# Display_LED_Monitor.net
KiCad netlist of a schematic drawn in Altium Designer
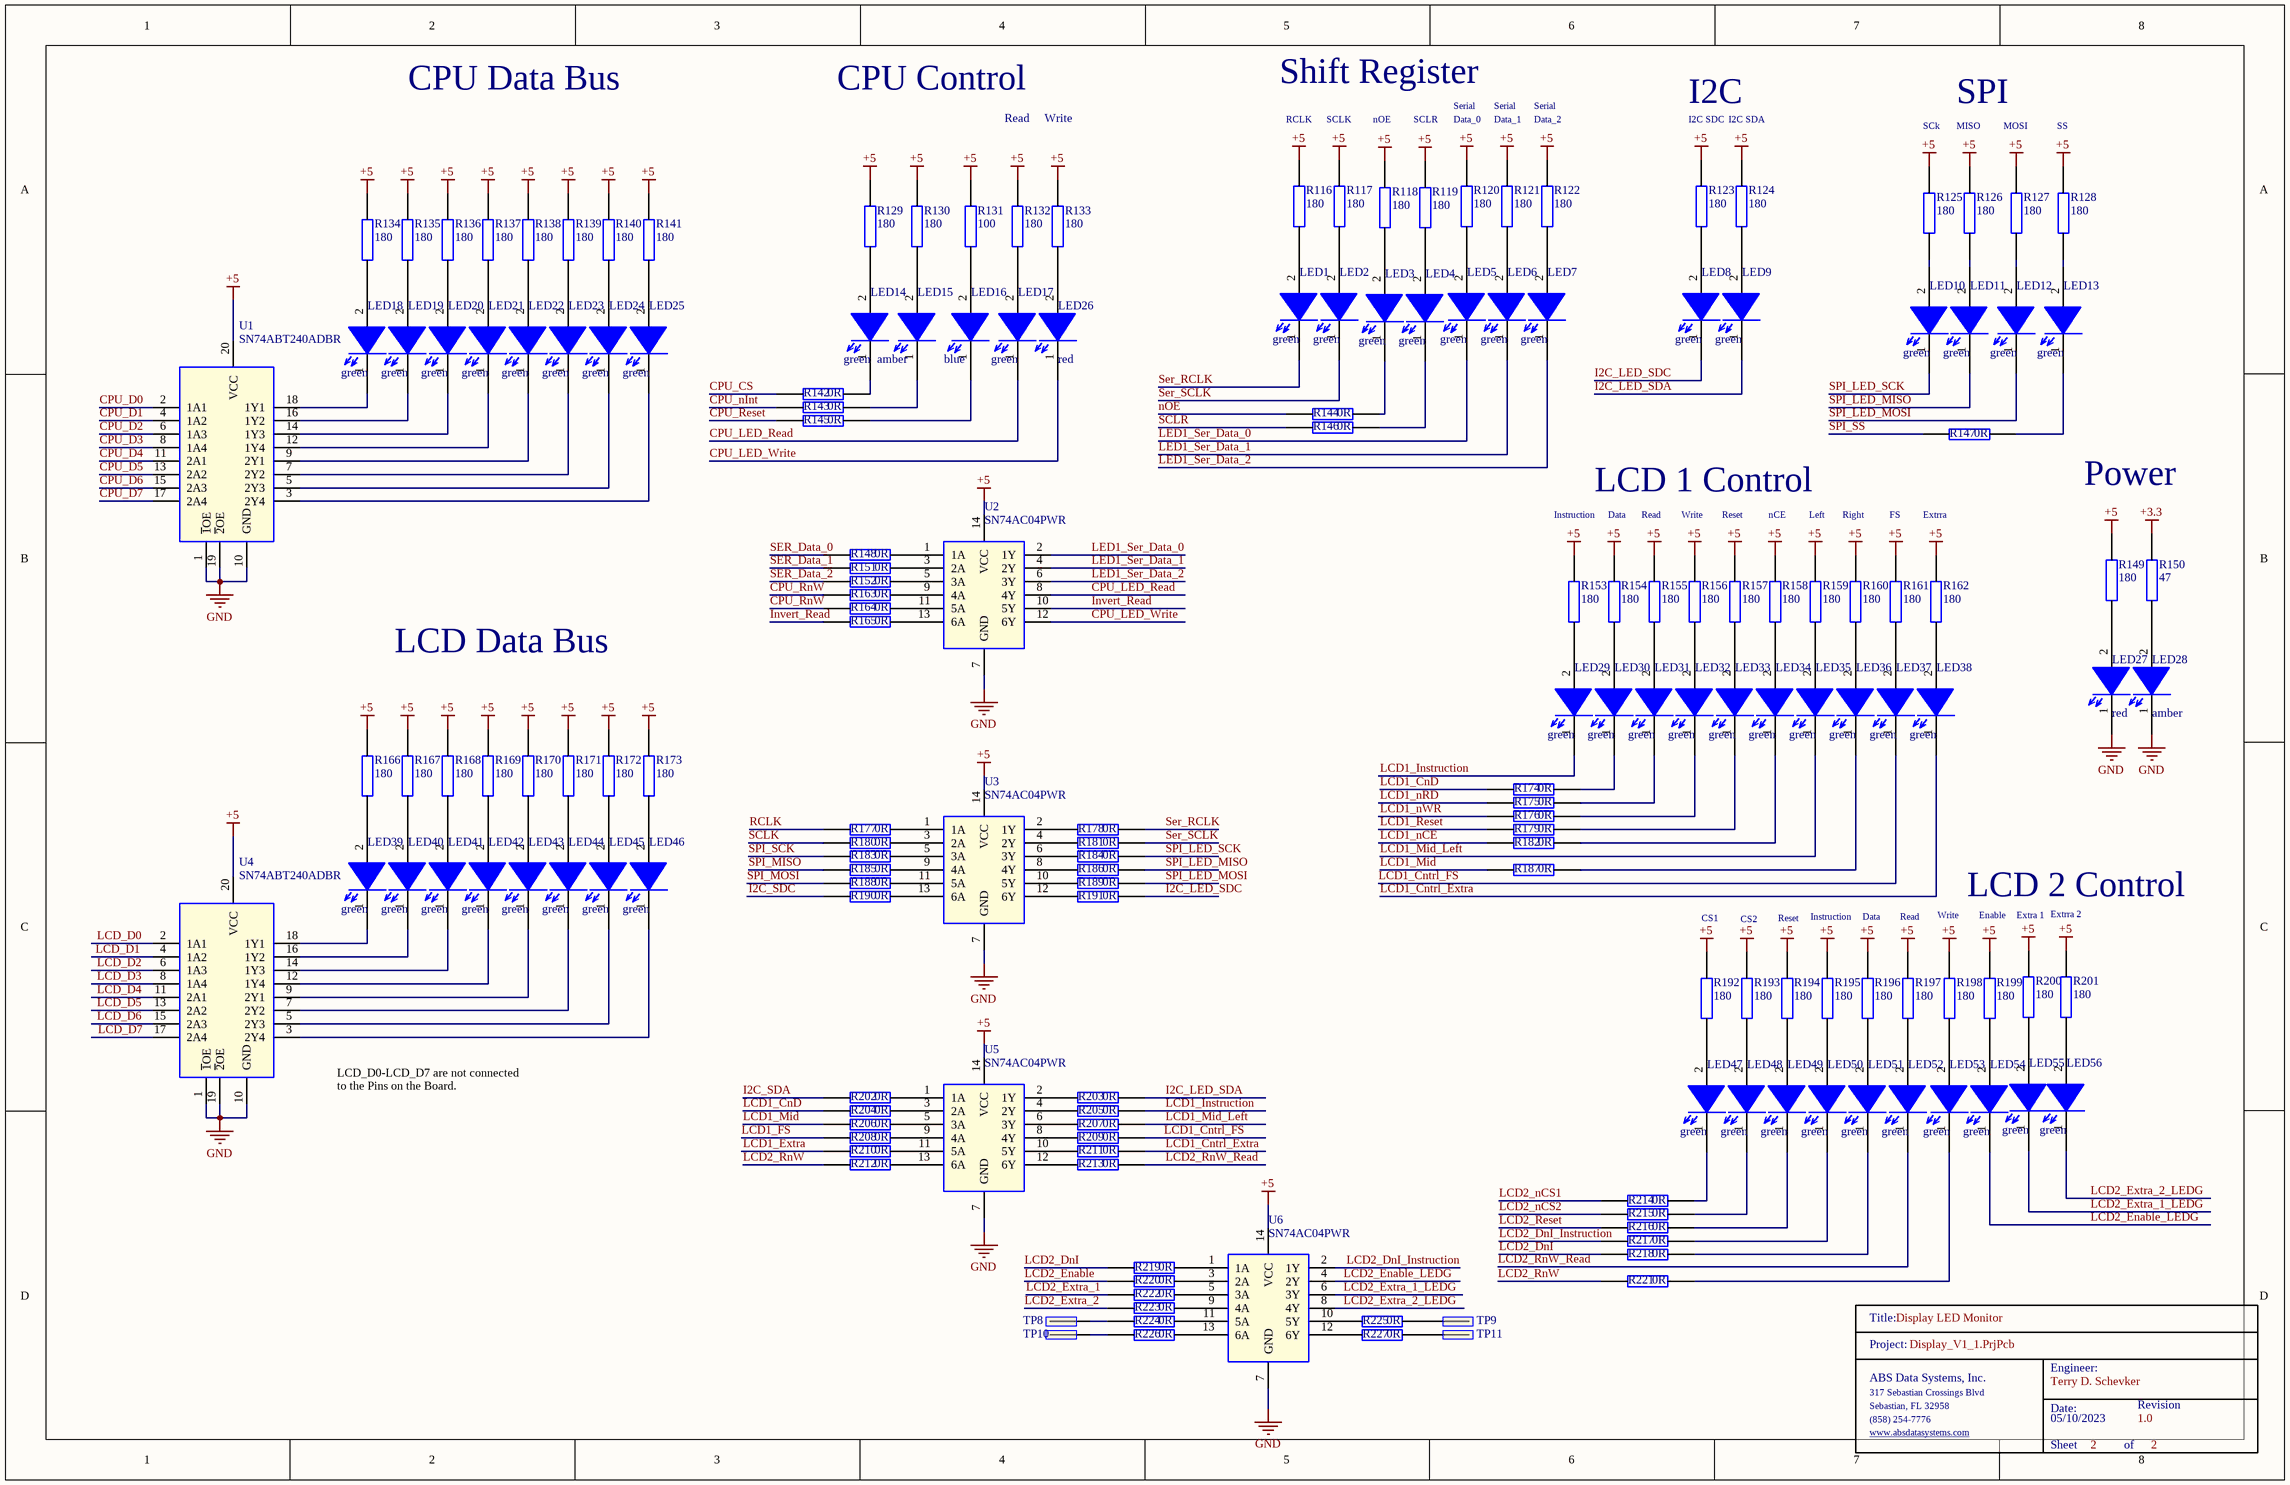
[diagram p0: Display_LED_Monitor.SchDoc]

(export (version "E")
  (design (tool "Eeschema 10.0.6"))
  (components
    (comp (ref "LED1")
      (value "green")
      (footprint "0603_Diode")
      (description "Wurth Elektronik 0603 green")
      (fields
        (field (name "MANUFACTURER") "Wurth Electronics")
        (field (name "MANUFACTURER PART NUMBER") "150060GS75000")
      )
      (libsource (lib "Misc") (part "150060GS75000"))
    )
    (comp (ref "LED2")
      (value "green")
      (footprint "0603_Diode")
      (description "Wurth Elektronik 0603 green")
      (fields
        (field (name "MANUFACTURER") "Wurth Electronics")
        (field (name "MANUFACTURER PART NUMBER") "150060GS75000")
      )
      (libsource (lib "Misc") (part "150060GS75000"))
    )
    (comp (ref "LED3")
      (value "green")
      (footprint "0603_Diode")
      (description "Wurth Elektronik 0603 green")
      (fields
        (field (name "MANUFACTURER") "Wurth Electronics")
        (field (name "MANUFACTURER PART NUMBER") "150060GS75000")
      )
      (libsource (lib "Misc") (part "150060GS75000"))
    )
    (comp (ref "LED4")
      (value "green")
      (footprint "0603_Diode")
      (description "Wurth Elektronik 0603 green")
      (fields
        (field (name "MANUFACTURER") "Wurth Electronics")
        (field (name "MANUFACTURER PART NUMBER") "150060GS75000")
      )
      (libsource (lib "Misc") (part "150060GS75000"))
    )
    (comp (ref "LED5")
      (value "green")
      (footprint "0603_Diode")
      (description "Wurth Elektronik 0603 green")
      (fields
        (field (name "MANUFACTURER") "Wurth Electronics")
        (field (name "MANUFACTURER PART NUMBER") "150060GS75000")
      )
      (libsource (lib "Misc") (part "150060GS75000"))
    )
    (comp (ref "LED6")
      (value "green")
      (footprint "0603_Diode")
      (description "Wurth Elektronik 0603 green")
      (fields
        (field (name "MANUFACTURER") "Wurth Electronics")
        (field (name "MANUFACTURER PART NUMBER") "150060GS75000")
      )
      (libsource (lib "Misc") (part "150060GS75000"))
    )
    (comp (ref "LED7")
      (value "green")
      (footprint "0603_Diode")
      (description "Wurth Elektronik 0603 green")
      (fields
        (field (name "MANUFACTURER") "Wurth Electronics")
        (field (name "MANUFACTURER PART NUMBER") "150060GS75000")
      )
      (libsource (lib "Misc") (part "150060GS75000"))
    )
    (comp (ref "LED8")
      (value "green")
      (footprint "0603_Diode")
      (description "Wurth Elektronik 0603 green")
      (fields
        (field (name "MANUFACTURER") "Wurth Electronics")
        (field (name "MANUFACTURER PART NUMBER") "150060GS75000")
      )
      (libsource (lib "Misc") (part "150060GS75000"))
    )
    (comp (ref "LED9")
      (value "green")
      (footprint "0603_Diode")
      (description "Wurth Elektronik 0603 green")
      (fields
        (field (name "MANUFACTURER") "Wurth Electronics")
        (field (name "MANUFACTURER PART NUMBER") "150060GS75000")
      )
      (libsource (lib "Misc") (part "150060GS75000"))
    )
    (comp (ref "LED10")
      (value "green")
      (footprint "0603_Diode")
      (description "Wurth Elektronik 0603 green")
      (fields
        (field (name "MANUFACTURER") "Wurth Electronics")
        (field (name "MANUFACTURER PART NUMBER") "150060GS75000")
      )
      (libsource (lib "Misc") (part "150060GS75000"))
    )
    (comp (ref "LED11")
      (value "green")
      (footprint "0603_Diode")
      (description "Wurth Elektronik 0603 green")
      (fields
        (field (name "MANUFACTURER") "Wurth Electronics")
        (field (name "MANUFACTURER PART NUMBER") "150060GS75000")
      )
      (libsource (lib "Misc") (part "150060GS75000"))
    )
    (comp (ref "LED12")
      (value "green")
      (footprint "0603_Diode")
      (description "Wurth Elektronik 0603 green")
      (fields
        (field (name "MANUFACTURER") "Wurth Electronics")
        (field (name "MANUFACTURER PART NUMBER") "150060GS75000")
      )
      (libsource (lib "Misc") (part "150060GS75000"))
    )
    (comp (ref "LED13")
      (value "green")
      (footprint "0603_Diode")
      (description "Wurth Elektronik 0603 green")
      (fields
        (field (name "MANUFACTURER") "Wurth Electronics")
        (field (name "MANUFACTURER PART NUMBER") "150060GS75000")
      )
      (libsource (lib "Misc") (part "150060GS75000"))
    )
    (comp (ref "LED14")
      (value "green")
      (footprint "0603_Diode")
      (description "Wurth Elektronik 0603 green")
      (fields
        (field (name "MANUFACTURER") "Wurth Electronics")
        (field (name "MANUFACTURER PART NUMBER") "150060GS75000")
      )
      (libsource (lib "Misc") (part "150060GS75000"))
    )
    (comp (ref "LED15")
      (value "amber")
      (footprint "0603_Diode")
      (description "Wurth Elektronik 0603 amber")
      (fields
        (field (name "MANUFACTURER") "Wurth Electronics")
        (field (name "MANUFACTURER PART NUMBER") "150060GS75000")
      )
      (libsource (lib "Misc") (part "150060AS75000"))
    )
    (comp (ref "LED16")
      (value "blue")
      (footprint "0603_Diode")
      (description "Wurth Elektronik 0603 blue")
      (fields
        (field (name "MANUFACTURER") "Wurth Electronics")
        (field (name "MANUFACTURER PART NUMBER") "150060GS75000")
      )
      (libsource (lib "Misc") (part "150060BS75000"))
    )
    (comp (ref "LED17")
      (value "green")
      (footprint "0603_Diode")
      (description "Wurth Elektronik 0603 green")
      (fields
        (field (name "MANUFACTURER") "Wurth Electronics")
        (field (name "MANUFACTURER PART NUMBER") "150060GS75000")
      )
      (libsource (lib "Misc") (part "150060GS75000"))
    )
    (comp (ref "LED18")
      (value "green")
      (footprint "0603_Diode")
      (description "Wurth Elektronik 0603 green")
      (fields
        (field (name "MANUFACTURER") "Wurth Electronics")
        (field (name "MANUFACTURER PART NUMBER") "150060GS75000")
      )
      (libsource (lib "Misc") (part "150060GS75000"))
    )
    (comp (ref "LED19")
      (value "green")
      (footprint "0603_Diode")
      (description "Wurth Elektronik 0603 green")
      (fields
        (field (name "MANUFACTURER") "Wurth Electronics")
        (field (name "MANUFACTURER PART NUMBER") "150060GS75000")
      )
      (libsource (lib "Misc") (part "150060GS75000"))
    )
    (comp (ref "LED20")
      (value "green")
      (footprint "0603_Diode")
      (description "Wurth Elektronik 0603 green")
      (fields
        (field (name "MANUFACTURER") "Wurth Electronics")
        (field (name "MANUFACTURER PART NUMBER") "150060GS75000")
      )
      (libsource (lib "Misc") (part "150060GS75000"))
    )
    (comp (ref "LED21")
      (value "green")
      (footprint "0603_Diode")
      (description "Wurth Elektronik 0603 green")
      (fields
        (field (name "MANUFACTURER") "Wurth Electronics")
        (field (name "MANUFACTURER PART NUMBER") "150060GS75000")
      )
      (libsource (lib "Misc") (part "150060GS75000"))
    )
    (comp (ref "LED22")
      (value "green")
      (footprint "0603_Diode")
      (description "Wurth Elektronik 0603 green")
      (fields
        (field (name "MANUFACTURER") "Wurth Electronics")
        (field (name "MANUFACTURER PART NUMBER") "150060GS75000")
      )
      (libsource (lib "Misc") (part "150060GS75000"))
    )
    (comp (ref "LED23")
      (value "green")
      (footprint "0603_Diode")
      (description "Wurth Elektronik 0603 green")
      (fields
        (field (name "MANUFACTURER") "Wurth Electronics")
        (field (name "MANUFACTURER PART NUMBER") "150060GS75000")
      )
      (libsource (lib "Misc") (part "150060GS75000"))
    )
    (comp (ref "LED24")
      (value "green")
      (footprint "0603_Diode")
      (description "Wurth Elektronik 0603 green")
      (fields
        (field (name "MANUFACTURER") "Wurth Electronics")
        (field (name "MANUFACTURER PART NUMBER") "150060GS75000")
      )
      (libsource (lib "Misc") (part "150060GS75000"))
    )
    (comp (ref "LED25")
      (value "green")
      (footprint "0603_Diode")
      (description "Wurth Elektronik 0603 green")
      (fields
        (field (name "MANUFACTURER") "Wurth Electronics")
        (field (name "MANUFACTURER PART NUMBER") "150060GS75000")
      )
      (libsource (lib "Misc") (part "150060GS75000"))
    )
    (comp (ref "LED26")
      (value "red")
      (footprint "0603_Diode")
      (description "Wurth Elektronik 0603 red")
      (fields
        (field (name "MANUFACTURER") "Wurth Electronics")
        (field (name "MANUFACTURER PART NUMBER") "150060GS75000")
      )
      (libsource (lib "Misc") (part "150060RS75000"))
    )
    (comp (ref "LED27")
      (value "red")
      (footprint "0603_Diode")
      (description "Wurth Elektronik 0603 red")
      (fields
        (field (name "MANUFACTURER") "Wurth Electronics")
        (field (name "MANUFACTURER PART NUMBER") "150060GS75000")
      )
      (libsource (lib "Misc") (part "150060RS75000"))
    )
    (comp (ref "LED28")
      (value "amber")
      (footprint "0603_Diode")
      (description "Wurth Elektronik 0603 amber")
      (fields
        (field (name "MANUFACTURER") "Wurth Electronics")
        (field (name "MANUFACTURER PART NUMBER") "150060GS75000")
      )
      (libsource (lib "Misc") (part "150060AS75000"))
    )
    (comp (ref "LED29")
      (value "green")
      (footprint "0603_Diode")
      (description "Wurth Elektronik 0603 green")
      (fields
        (field (name "MANUFACTURER") "Wurth Electronics")
        (field (name "MANUFACTURER PART NUMBER") "150060GS75000")
      )
      (libsource (lib "Misc") (part "150060GS75000"))
    )
    (comp (ref "LED30")
      (value "green")
      (footprint "0603_Diode")
      (description "Wurth Elektronik 0603 green")
      (fields
        (field (name "MANUFACTURER") "Wurth Electronics")
        (field (name "MANUFACTURER PART NUMBER") "150060GS75000")
      )
      (libsource (lib "Misc") (part "150060GS75000"))
    )
    (comp (ref "LED31")
      (value "green")
      (footprint "0603_Diode")
      (description "Wurth Elektronik 0603 green")
      (fields
        (field (name "MANUFACTURER") "Wurth Electronics")
        (field (name "MANUFACTURER PART NUMBER") "150060GS75000")
      )
      (libsource (lib "Misc") (part "150060GS75000"))
    )
    (comp (ref "LED32")
      (value "green")
      (footprint "0603_Diode")
      (description "Wurth Elektronik 0603 green")
      (fields
        (field (name "MANUFACTURER") "Wurth Electronics")
        (field (name "MANUFACTURER PART NUMBER") "150060GS75000")
      )
      (libsource (lib "Misc") (part "150060GS75000"))
    )
    (comp (ref "LED33")
      (value "green")
      (footprint "0603_Diode")
      (description "Wurth Elektronik 0603 green")
      (fields
        (field (name "MANUFACTURER") "Wurth Electronics")
        (field (name "MANUFACTURER PART NUMBER") "150060GS75000")
      )
      (libsource (lib "Misc") (part "150060GS75000"))
    )
    (comp (ref "LED34")
      (value "green")
      (footprint "0603_Diode")
      (description "Wurth Elektronik 0603 green")
      (fields
        (field (name "MANUFACTURER") "Wurth Electronics")
        (field (name "MANUFACTURER PART NUMBER") "150060GS75000")
      )
      (libsource (lib "Misc") (part "150060GS75000"))
    )
    (comp (ref "LED35")
      (value "green")
      (footprint "0603_Diode")
      (description "Wurth Elektronik 0603 green")
      (fields
        (field (name "MANUFACTURER") "Wurth Electronics")
        (field (name "MANUFACTURER PART NUMBER") "150060GS75000")
      )
      (libsource (lib "Misc") (part "150060GS75000"))
    )
    (comp (ref "LED36")
      (value "green")
      (footprint "0603_Diode")
      (description "Wurth Elektronik 0603 green")
      (fields
        (field (name "MANUFACTURER") "Wurth Electronics")
        (field (name "MANUFACTURER PART NUMBER") "150060GS75000")
      )
      (libsource (lib "Misc") (part "150060GS75000"))
    )
    (comp (ref "LED37")
      (value "green")
      (footprint "0603_Diode")
      (description "Wurth Elektronik 0603 green")
      (fields
        (field (name "MANUFACTURER") "Wurth Electronics")
        (field (name "MANUFACTURER PART NUMBER") "150060GS75000")
      )
      (libsource (lib "Misc") (part "150060GS75000"))
    )
    (comp (ref "LED38")
      (value "green")
      (footprint "0603_Diode")
      (description "Wurth Elektronik 0603 green")
      (fields
        (field (name "MANUFACTURER") "Wurth Electronics")
        (field (name "MANUFACTURER PART NUMBER") "150060GS75000")
      )
      (libsource (lib "Misc") (part "150060GS75000"))
    )
    (comp (ref "LED39")
      (value "green")
      (footprint "0603_Diode")
      (description "Wurth Elektronik 0603 green")
      (fields
        (field (name "MANUFACTURER") "Wurth Electronics")
        (field (name "MANUFACTURER PART NUMBER") "150060GS75000")
      )
      (libsource (lib "Misc") (part "150060GS75000"))
    )
    (comp (ref "LED40")
      (value "green")
      (footprint "0603_Diode")
      (description "Wurth Elektronik 0603 green")
      (fields
        (field (name "MANUFACTURER") "Wurth Electronics")
        (field (name "MANUFACTURER PART NUMBER") "150060GS75000")
      )
      (libsource (lib "Misc") (part "150060GS75000"))
    )
    (comp (ref "LED41")
      (value "green")
      (footprint "0603_Diode")
      (description "Wurth Elektronik 0603 green")
      (fields
        (field (name "MANUFACTURER") "Wurth Electronics")
        (field (name "MANUFACTURER PART NUMBER") "150060GS75000")
      )
      (libsource (lib "Misc") (part "150060GS75000"))
    )
    (comp (ref "LED42")
      (value "green")
      (footprint "0603_Diode")
      (description "Wurth Elektronik 0603 green")
      (fields
        (field (name "MANUFACTURER") "Wurth Electronics")
        (field (name "MANUFACTURER PART NUMBER") "150060GS75000")
      )
      (libsource (lib "Misc") (part "150060GS75000"))
    )
    (comp (ref "LED43")
      (value "green")
      (footprint "0603_Diode")
      (description "Wurth Elektronik 0603 green")
      (fields
        (field (name "MANUFACTURER") "Wurth Electronics")
        (field (name "MANUFACTURER PART NUMBER") "150060GS75000")
      )
      (libsource (lib "Misc") (part "150060GS75000"))
    )
    (comp (ref "LED44")
      (value "green")
      (footprint "0603_Diode")
      (description "Wurth Elektronik 0603 green")
      (fields
        (field (name "MANUFACTURER") "Wurth Electronics")
        (field (name "MANUFACTURER PART NUMBER") "150060GS75000")
      )
      (libsource (lib "Misc") (part "150060GS75000"))
    )
    (comp (ref "LED45")
      (value "green")
      (footprint "0603_Diode")
      (description "Wurth Elektronik 0603 green")
      (fields
        (field (name "MANUFACTURER") "Wurth Electronics")
        (field (name "MANUFACTURER PART NUMBER") "150060GS75000")
      )
      (libsource (lib "Misc") (part "150060GS75000"))
    )
    (comp (ref "LED46")
      (value "green")
      (footprint "0603_Diode")
      (description "Wurth Elektronik 0603 green")
      (fields
        (field (name "MANUFACTURER") "Wurth Electronics")
        (field (name "MANUFACTURER PART NUMBER") "150060GS75000")
      )
      (libsource (lib "Misc") (part "150060GS75000"))
    )
    (comp (ref "LED47")
      (value "green")
      (footprint "0603_Diode")
      (description "Wurth Elektronik 0603 green")
      (fields
        (field (name "MANUFACTURER") "Wurth Electronics")
        (field (name "MANUFACTURER PART NUMBER") "150060GS75000")
      )
      (libsource (lib "Misc") (part "150060GS75000"))
    )
    (comp (ref "LED48")
      (value "green")
      (footprint "0603_Diode")
      (description "Wurth Elektronik 0603 green")
      (fields
        (field (name "MANUFACTURER") "Wurth Electronics")
        (field (name "MANUFACTURER PART NUMBER") "150060GS75000")
      )
      (libsource (lib "Misc") (part "150060GS75000"))
    )
    (comp (ref "LED49")
      (value "green")
      (footprint "0603_Diode")
      (description "Wurth Elektronik 0603 green")
      (fields
        (field (name "MANUFACTURER") "Wurth Electronics")
        (field (name "MANUFACTURER PART NUMBER") "150060GS75000")
      )
      (libsource (lib "Misc") (part "150060GS75000"))
    )
    (comp (ref "LED50")
      (value "green")
      (footprint "0603_Diode")
      (description "Wurth Elektronik 0603 green")
      (fields
        (field (name "MANUFACTURER") "Wurth Electronics")
        (field (name "MANUFACTURER PART NUMBER") "150060GS75000")
      )
      (libsource (lib "Misc") (part "150060GS75000"))
    )
    (comp (ref "LED51")
      (value "green")
      (footprint "0603_Diode")
      (description "Wurth Elektronik 0603 green")
      (fields
        (field (name "MANUFACTURER") "Wurth Electronics")
        (field (name "MANUFACTURER PART NUMBER") "150060GS75000")
      )
      (libsource (lib "Misc") (part "150060GS75000"))
    )
    (comp (ref "LED52")
      (value "green")
      (footprint "0603_Diode")
      (description "Wurth Elektronik 0603 green")
      (fields
        (field (name "MANUFACTURER") "Wurth Electronics")
        (field (name "MANUFACTURER PART NUMBER") "150060GS75000")
      )
      (libsource (lib "Misc") (part "150060GS75000"))
    )
    (comp (ref "LED53")
      (value "green")
      (footprint "0603_Diode")
      (description "Wurth Elektronik 0603 green")
      (fields
        (field (name "MANUFACTURER") "Wurth Electronics")
        (field (name "MANUFACTURER PART NUMBER") "150060GS75000")
      )
      (libsource (lib "Misc") (part "150060GS75000"))
    )
    (comp (ref "LED54")
      (value "green")
      (footprint "0603_Diode")
      (description "Wurth Elektronik 0603 green")
      (fields
        (field (name "MANUFACTURER") "Wurth Electronics")
        (field (name "MANUFACTURER PART NUMBER") "150060GS75000")
      )
      (libsource (lib "Misc") (part "150060GS75000"))
    )
    (comp (ref "LED55")
      (value "green")
      (footprint "0603_Diode")
      (description "Wurth Elektronik 0603 green")
      (fields
        (field (name "MANUFACTURER") "Wurth Electronics")
        (field (name "MANUFACTURER PART NUMBER") "150060GS75000")
      )
      (libsource (lib "Misc") (part "150060GS75000"))
    )
    (comp (ref "LED56")
      (value "green")
      (footprint "0603_Diode")
      (description "Wurth Elektronik 0603 green")
      (fields
        (field (name "MANUFACTURER") "Wurth Electronics")
        (field (name "MANUFACTURER PART NUMBER") "150060GS75000")
      )
      (libsource (lib "Misc") (part "150060GS75000"))
    )
    (comp (ref "R116")
      (value "180")
      (footprint "0603")
      (description "YAGEO 0603 180 ohm")
      (fields
        (field (name "MOUSER PART NUMBER") "603-RC0603JR-070RL")
        (field (name "MANUFACTURER_PART_NUMBER") "RC0603JR-070RL")
      )
      (libsource (lib "Resistors") (part "RC0603FR-13180RL"))
    )
    (comp (ref "R117")
      (value "180")
      (footprint "0603")
      (description "YAGEO 0603 180 ohm")
      (fields
        (field (name "MOUSER PART NUMBER") "603-RC0603JR-070RL")
        (field (name "MANUFACTURER_PART_NUMBER") "RC0603JR-070RL")
      )
      (libsource (lib "Resistors") (part "RC0603FR-13180RL"))
    )
    (comp (ref "R118")
      (value "180")
      (footprint "0603")
      (description "YAGEO 0603 180 ohm")
      (fields
        (field (name "MOUSER PART NUMBER") "603-RC0603JR-070RL")
        (field (name "MANUFACTURER_PART_NUMBER") "RC0603JR-070RL")
      )
      (libsource (lib "Resistors") (part "RC0603FR-13180RL"))
    )
    (comp (ref "R119")
      (value "180")
      (footprint "0603")
      (description "YAGEO 0603 180 ohm")
      (fields
        (field (name "MOUSER PART NUMBER") "603-RC0603JR-070RL")
        (field (name "MANUFACTURER_PART_NUMBER") "RC0603JR-070RL")
      )
      (libsource (lib "Resistors") (part "RC0603FR-13180RL"))
    )
    (comp (ref "R120")
      (value "180")
      (footprint "0603")
      (description "YAGEO 0603 180 ohm")
      (fields
        (field (name "MOUSER PART NUMBER") "603-RC0603JR-070RL")
        (field (name "MANUFACTURER_PART_NUMBER") "RC0603JR-070RL")
      )
      (libsource (lib "Resistors") (part "RC0603FR-13180RL"))
    )
    (comp (ref "R121")
      (value "180")
      (footprint "0603")
      (description "YAGEO 0603 180 ohm")
      (fields
        (field (name "MOUSER PART NUMBER") "603-RC0603JR-070RL")
        (field (name "MANUFACTURER_PART_NUMBER") "RC0603JR-070RL")
      )
      (libsource (lib "Resistors") (part "RC0603FR-13180RL"))
    )
    (comp (ref "R122")
      (value "180")
      (footprint "0603")
      (description "YAGEO 0603 180 ohm")
      (fields
        (field (name "MOUSER PART NUMBER") "603-RC0603JR-070RL")
        (field (name "MANUFACTURER_PART_NUMBER") "RC0603JR-070RL")
      )
      (libsource (lib "Resistors") (part "RC0603FR-13180RL"))
    )
    (comp (ref "R123")
      (value "180")
      (footprint "0603")
      (description "YAGEO 0603 180 ohm")
      (fields
        (field (name "MOUSER PART NUMBER") "603-RC0603JR-070RL")
        (field (name "MANUFACTURER_PART_NUMBER") "RC0603JR-070RL")
      )
      (libsource (lib "Resistors") (part "RC0603FR-13180RL"))
    )
    (comp (ref "R124")
      (value "180")
      (footprint "0603")
      (description "YAGEO 0603 180 ohm")
      (fields
        (field (name "MOUSER PART NUMBER") "603-RC0603JR-070RL")
        (field (name "MANUFACTURER_PART_NUMBER") "RC0603JR-070RL")
      )
      (libsource (lib "Resistors") (part "RC0603FR-13180RL"))
    )
    (comp (ref "R125")
      (value "180")
      (footprint "0603")
      (description "YAGEO 0603 180 ohm")
      (fields
        (field (name "MOUSER PART NUMBER") "603-RC0603JR-070RL")
        (field (name "MANUFACTURER_PART_NUMBER") "RC0603JR-070RL")
      )
      (libsource (lib "Resistors") (part "RC0603FR-13180RL"))
    )
    (comp (ref "R126")
      (value "180")
      (footprint "0603")
      (description "YAGEO 0603 180 ohm")
      (fields
        (field (name "MOUSER PART NUMBER") "603-RC0603JR-070RL")
        (field (name "MANUFACTURER_PART_NUMBER") "RC0603JR-070RL")
      )
      (libsource (lib "Resistors") (part "RC0603FR-13180RL"))
    )
    (comp (ref "R127")
      (value "180")
      (footprint "0603")
      (description "YAGEO 0603 180 ohm")
      (fields
        (field (name "MOUSER PART NUMBER") "603-RC0603JR-070RL")
        (field (name "MANUFACTURER_PART_NUMBER") "RC0603JR-070RL")
      )
      (libsource (lib "Resistors") (part "RC0603FR-13180RL"))
    )
    (comp (ref "R128")
      (value "180")
      (footprint "0603")
      (description "YAGEO 0603 180 ohm")
      (fields
        (field (name "MOUSER PART NUMBER") "603-RC0603JR-070RL")
        (field (name "MANUFACTURER_PART_NUMBER") "RC0603JR-070RL")
      )
      (libsource (lib "Resistors") (part "RC0603FR-13180RL"))
    )
    (comp (ref "R129")
      (value "180")
      (footprint "0603")
      (description "YAGEO 0603 180 ohm")
      (fields
        (field (name "MOUSER PART NUMBER") "603-RC0603JR-070RL")
        (field (name "MANUFACTURER_PART_NUMBER") "RC0603JR-070RL")
      )
      (libsource (lib "Resistors") (part "RC0603FR-13180RL"))
    )
    (comp (ref "R130")
      (value "180")
      (footprint "0603")
      (description "YAGEO 0603 180 ohm")
      (fields
        (field (name "MOUSER PART NUMBER") "603-RC0603JR-070RL")
        (field (name "MANUFACTURER_PART_NUMBER") "RC0603JR-070RL")
      )
      (libsource (lib "Resistors") (part "RC0603FR-13180RL"))
    )
    (comp (ref "R131")
      (value "100")
      (footprint "0603")
      (description "YAGEO 0603 100 ohm")
      (fields
        (field (name "MOUSER PART NUMBER") "603-RC0603JR-070RL")
        (field (name "MANUFACTURER_PART_NUMBER") "RC0603JR-070RL")
      )
      (libsource (lib "Resistors") (part "RC0603FR-10100RL"))
    )
    (comp (ref "R132")
      (value "180")
      (footprint "0603")
      (description "YAGEO 0603 180 ohm")
      (fields
        (field (name "MOUSER PART NUMBER") "603-RC0603JR-070RL")
        (field (name "MANUFACTURER_PART_NUMBER") "RC0603JR-070RL")
      )
      (libsource (lib "Resistors") (part "RC0603FR-13180RL"))
    )
    (comp (ref "R133")
      (value "180")
      (footprint "0603")
      (description "YAGEO 0603 180 ohm")
      (fields
        (field (name "MOUSER PART NUMBER") "603-RC0603JR-070RL")
        (field (name "MANUFACTURER_PART_NUMBER") "RC0603JR-070RL")
      )
      (libsource (lib "Resistors") (part "RC0603FR-13180RL"))
    )
    (comp (ref "R134")
      (value "180")
      (footprint "0603")
      (description "YAGEO 0603 180 ohm")
      (fields
        (field (name "MOUSER PART NUMBER") "603-RC0603JR-070RL")
        (field (name "MANUFACTURER_PART_NUMBER") "RC0603JR-070RL")
      )
      (libsource (lib "Resistors") (part "RC0603FR-13180RL"))
    )
    (comp (ref "R135")
      (value "180")
      (footprint "0603")
      (description "YAGEO 0603 180 ohm")
      (fields
        (field (name "MOUSER PART NUMBER") "603-RC0603JR-070RL")
        (field (name "MANUFACTURER_PART_NUMBER") "RC0603JR-070RL")
      )
      (libsource (lib "Resistors") (part "RC0603FR-13180RL"))
    )
    (comp (ref "R136")
      (value "180")
      (footprint "0603")
      (description "YAGEO 0603 180 ohm")
      (fields
        (field (name "MOUSER PART NUMBER") "603-RC0603JR-070RL")
        (field (name "MANUFACTURER_PART_NUMBER") "RC0603JR-070RL")
      )
      (libsource (lib "Resistors") (part "RC0603FR-13180RL"))
    )
    (comp (ref "R137")
      (value "180")
      (footprint "0603")
      (description "YAGEO 0603 180 ohm")
      (fields
        (field (name "MOUSER PART NUMBER") "603-RC0603JR-070RL")
        (field (name "MANUFACTURER_PART_NUMBER") "RC0603JR-070RL")
      )
      (libsource (lib "Resistors") (part "RC0603FR-13180RL"))
    )
    (comp (ref "R138")
      (value "180")
      (footprint "0603")
      (description "YAGEO 0603 180 ohm")
      (fields
        (field (name "MOUSER PART NUMBER") "603-RC0603JR-070RL")
        (field (name "MANUFACTURER_PART_NUMBER") "RC0603JR-070RL")
      )
      (libsource (lib "Resistors") (part "RC0603FR-13180RL"))
    )
    (comp (ref "R139")
      (value "180")
      (footprint "0603")
      (description "YAGEO 0603 180 ohm")
      (fields
        (field (name "MOUSER PART NUMBER") "603-RC0603JR-070RL")
        (field (name "MANUFACTURER_PART_NUMBER") "RC0603JR-070RL")
      )
      (libsource (lib "Resistors") (part "RC0603FR-13180RL"))
    )
    (comp (ref "R140")
      (value "180")
      (footprint "0603")
      (description "YAGEO 0603 180 ohm")
      (fields
        (field (name "MOUSER PART NUMBER") "603-RC0603JR-070RL")
        (field (name "MANUFACTURER_PART_NUMBER") "RC0603JR-070RL")
      )
      (libsource (lib "Resistors") (part "RC0603FR-13180RL"))
    )
    (comp (ref "R141")
      (value "180")
      (footprint "0603")
      (description "YAGEO 0603 180 ohm")
      (fields
        (field (name "MOUSER PART NUMBER") "603-RC0603JR-070RL")
        (field (name "MANUFACTURER_PART_NUMBER") "RC0603JR-070RL")
      )
      (libsource (lib "Resistors") (part "RC0603FR-13180RL"))
    )
    (comp (ref "R142")
      (value "0R")
      (footprint "0603")
      (description "YAGEO 0603 0 ohm")
      (fields
        (field (name "MOUSER PART NUMBER") "603-RC0603JR-070RL")
        (field (name "MANUFACTURER_PART_NUMBER") "RC0603JR-070RL")
      )
      (libsource (lib "Resistors") (part "RC0603JR-070RL"))
    )
    (comp (ref "R143")
      (value "0R")
      (footprint "0603")
      (description "YAGEO 0603 0 ohm")
      (fields
        (field (name "MOUSER PART NUMBER") "603-RC0603JR-070RL")
        (field (name "MANUFACTURER_PART_NUMBER") "RC0603JR-070RL")
      )
      (libsource (lib "Resistors") (part "RC0603JR-070RL"))
    )
    (comp (ref "R144")
      (value "0R")
      (footprint "0603")
      (description "YAGEO 0603 0 ohm")
      (fields
        (field (name "MOUSER PART NUMBER") "603-RC0603JR-070RL")
        (field (name "MANUFACTURER_PART_NUMBER") "RC0603JR-070RL")
      )
      (libsource (lib "Resistors") (part "RC0603JR-070RL"))
    )
    (comp (ref "R145")
      (value "0R")
      (footprint "0603")
      (description "YAGEO 0603 0 ohm")
      (fields
        (field (name "MOUSER PART NUMBER") "603-RC0603JR-070RL")
        (field (name "MANUFACTURER_PART_NUMBER") "RC0603JR-070RL")
      )
      (libsource (lib "Resistors") (part "RC0603JR-070RL"))
    )
    (comp (ref "R146")
      (value "0R")
      (footprint "0603")
      (description "YAGEO 0603 0 ohm")
      (fields
        (field (name "MOUSER PART NUMBER") "603-RC0603JR-070RL")
        (field (name "MANUFACTURER_PART_NUMBER") "RC0603JR-070RL")
      )
      (libsource (lib "Resistors") (part "RC0603JR-070RL"))
    )
    (comp (ref "R147")
      (value "0R")
      (footprint "0603")
      (description "YAGEO 0603 0 ohm")
      (fields
        (field (name "MOUSER PART NUMBER") "603-RC0603JR-070RL")
        (field (name "MANUFACTURER_PART_NUMBER") "RC0603JR-070RL")
      )
      (libsource (lib "Resistors") (part "RC0603JR-070RL"))
    )
    (comp (ref "R148")
      (value "0R")
      (footprint "0603")
      (description "YAGEO 0603 0 ohm")
      (fields
        (field (name "MOUSER PART NUMBER") "603-RC0603JR-070RL")
        (field (name "MANUFACTURER_PART_NUMBER") "RC0603JR-070RL")
      )
      (libsource (lib "Resistors") (part "RC0603JR-070RL"))
    )
    (comp (ref "R149")
      (value "180")
      (footprint "0603")
      (description "YAGEO 0603 180 ohm")
      (fields
        (field (name "MOUSER PART NUMBER") "603-RC0603JR-070RL")
        (field (name "MANUFACTURER_PART_NUMBER") "RC0603JR-070RL")
      )
      (libsource (lib "Resistors") (part "RC0603FR-13180RL"))
    )
    (comp (ref "R150")
      (value "47")
      (footprint "0603")
      (description "YAGEO 0603 47")
      (fields
        (field (name "MOUSER PART NUMBER") "603-RC0603JR-070RL")
        (field (name "MANUFACTURER_PART_NUMBER") "RC0603JR-070RL")
      )
      (libsource (lib "Resistors") (part "RC0603FR-0747KL"))
    )
    (comp (ref "R151")
      (value "0R")
      (footprint "0603")
      (description "YAGEO 0603 0 ohm")
      (fields
        (field (name "MOUSER PART NUMBER") "603-RC0603JR-070RL")
        (field (name "MANUFACTURER_PART_NUMBER") "RC0603JR-070RL")
      )
      (libsource (lib "Resistors") (part "RC0603JR-070RL"))
    )
    (comp (ref "R152")
      (value "0R")
      (footprint "0603")
      (description "YAGEO 0603 0 ohm")
      (fields
        (field (name "MOUSER PART NUMBER") "603-RC0603JR-070RL")
        (field (name "MANUFACTURER_PART_NUMBER") "RC0603JR-070RL")
      )
      (libsource (lib "Resistors") (part "RC0603JR-070RL"))
    )
    (comp (ref "R153")
      (value "180")
      (footprint "0603")
      (description "YAGEO 0603 180 ohm")
      (fields
        (field (name "MOUSER PART NUMBER") "603-RC0603JR-070RL")
        (field (name "MANUFACTURER_PART_NUMBER") "RC0603JR-070RL")
      )
      (libsource (lib "Resistors") (part "RC0603FR-13180RL"))
    )
    (comp (ref "R154")
      (value "180")
      (footprint "0603")
      (description "YAGEO 0603 180 ohm")
      (fields
        (field (name "MOUSER PART NUMBER") "603-RC0603JR-070RL")
        (field (name "MANUFACTURER_PART_NUMBER") "RC0603JR-070RL")
      )
      (libsource (lib "Resistors") (part "RC0603FR-13180RL"))
    )
    (comp (ref "R155")
      (value "180")
      (footprint "0603")
      (description "YAGEO 0603 180 ohm")
      (fields
        (field (name "MOUSER PART NUMBER") "603-RC0603JR-070RL")
        (field (name "MANUFACTURER_PART_NUMBER") "RC0603JR-070RL")
      )
      (libsource (lib "Resistors") (part "RC0603FR-13180RL"))
    )
    (comp (ref "R156")
      (value "180")
      (footprint "0603")
      (description "YAGEO 0603 180 ohm")
      (fields
        (field (name "MOUSER PART NUMBER") "603-RC0603JR-070RL")
        (field (name "MANUFACTURER_PART_NUMBER") "RC0603JR-070RL")
      )
      (libsource (lib "Resistors") (part "RC0603FR-13180RL"))
    )
    (comp (ref "R157")
      (value "180")
      (footprint "0603")
      (description "YAGEO 0603 180 ohm")
      (fields
        (field (name "MOUSER PART NUMBER") "603-RC0603JR-070RL")
        (field (name "MANUFACTURER_PART_NUMBER") "RC0603JR-070RL")
      )
      (libsource (lib "Resistors") (part "RC0603FR-13180RL"))
    )
    (comp (ref "R158")
      (value "180")
      (footprint "0603")
      (description "YAGEO 0603 180 ohm")
      (fields
        (field (name "MOUSER PART NUMBER") "603-RC0603JR-070RL")
        (field (name "MANUFACTURER_PART_NUMBER") "RC0603JR-070RL")
      )
      (libsource (lib "Resistors") (part "RC0603FR-13180RL"))
    )
    (comp (ref "R159")
      (value "180")
      (footprint "0603")
      (description "YAGEO 0603 180 ohm")
      (fields
        (field (name "MOUSER PART NUMBER") "603-RC0603JR-070RL")
        (field (name "MANUFACTURER_PART_NUMBER") "RC0603JR-070RL")
      )
      (libsource (lib "Resistors") (part "RC0603FR-13180RL"))
    )
    (comp (ref "R160")
      (value "180")
      (footprint "0603")
      (description "YAGEO 0603 180 ohm")
      (fields
        (field (name "MOUSER PART NUMBER") "603-RC0603JR-070RL")
        (field (name "MANUFACTURER_PART_NUMBER") "RC0603JR-070RL")
      )
      (libsource (lib "Resistors") (part "RC0603FR-13180RL"))
    )
    (comp (ref "R161")
      (value "180")
      (footprint "0603")
      (description "YAGEO 0603 180 ohm")
      (fields
        (field (name "MOUSER PART NUMBER") "603-RC0603JR-070RL")
        (field (name "MANUFACTURER_PART_NUMBER") "RC0603JR-070RL")
      )
      (libsource (lib "Resistors") (part "RC0603FR-13180RL"))
    )
    (comp (ref "R162")
      (value "180")
      (footprint "0603")
      (description "YAGEO 0603 180 ohm")
      (fields
        (field (name "MOUSER PART NUMBER") "603-RC0603JR-070RL")
        (field (name "MANUFACTURER_PART_NUMBER") "RC0603JR-070RL")
      )
      (libsource (lib "Resistors") (part "RC0603FR-13180RL"))
    )
    (comp (ref "R163")
      (value "0R")
      (footprint "0603")
      (description "YAGEO 0603 0 ohm")
      (fields
        (field (name "MOUSER PART NUMBER") "603-RC0603JR-070RL")
        (field (name "MANUFACTURER_PART_NUMBER") "RC0603JR-070RL")
      )
      (libsource (lib "Resistors") (part "RC0603JR-070RL"))
    )
    (comp (ref "R164")
      (value "0R")
      (footprint "0603")
      (description "YAGEO 0603 0 ohm")
      (fields
        (field (name "MOUSER PART NUMBER") "603-RC0603JR-070RL")
        (field (name "MANUFACTURER_PART_NUMBER") "RC0603JR-070RL")
      )
      (libsource (lib "Resistors") (part "RC0603JR-070RL"))
    )
    (comp (ref "R165")
      (value "0R")
      (footprint "0603")
      (description "YAGEO 0603 0 ohm")
      (fields
        (field (name "MOUSER PART NUMBER") "603-RC0603JR-070RL")
        (field (name "MANUFACTURER_PART_NUMBER") "RC0603JR-070RL")
      )
      (libsource (lib "Resistors") (part "RC0603JR-070RL"))
    )
    (comp (ref "R166")
      (value "180")
      (footprint "0603")
      (description "YAGEO 0603 180 ohm")
      (fields
        (field (name "MOUSER PART NUMBER") "603-RC0603JR-070RL")
        (field (name "MANUFACTURER_PART_NUMBER") "RC0603JR-070RL")
      )
      (libsource (lib "Resistors") (part "RC0603FR-13180RL"))
    )
    (comp (ref "R167")
      (value "180")
      (footprint "0603")
      (description "YAGEO 0603 180 ohm")
      (fields
        (field (name "MOUSER PART NUMBER") "603-RC0603JR-070RL")
        (field (name "MANUFACTURER_PART_NUMBER") "RC0603JR-070RL")
      )
      (libsource (lib "Resistors") (part "RC0603FR-13180RL"))
    )
    (comp (ref "R168")
      (value "180")
      (footprint "0603")
      (description "YAGEO 0603 180 ohm")
      (fields
        (field (name "MOUSER PART NUMBER") "603-RC0603JR-070RL")
        (field (name "MANUFACTURER_PART_NUMBER") "RC0603JR-070RL")
      )
      (libsource (lib "Resistors") (part "RC0603FR-13180RL"))
    )
    (comp (ref "R169")
      (value "180")
      (footprint "0603")
      (description "YAGEO 0603 180 ohm")
      (fields
        (field (name "MOUSER PART NUMBER") "603-RC0603JR-070RL")
        (field (name "MANUFACTURER_PART_NUMBER") "RC0603JR-070RL")
      )
      (libsource (lib "Resistors") (part "RC0603FR-13180RL"))
    )
    (comp (ref "R170")
      (value "180")
      (footprint "0603")
      (description "YAGEO 0603 180 ohm")
      (fields
        (field (name "MOUSER PART NUMBER") "603-RC0603JR-070RL")
        (field (name "MANUFACTURER_PART_NUMBER") "RC0603JR-070RL")
      )
      (libsource (lib "Resistors") (part "RC0603FR-13180RL"))
    )
    (comp (ref "R171")
      (value "180")
      (footprint "0603")
      (description "YAGEO 0603 180 ohm")
      (fields
        (field (name "MOUSER PART NUMBER") "603-RC0603JR-070RL")
        (field (name "MANUFACTURER_PART_NUMBER") "RC0603JR-070RL")
      )
      (libsource (lib "Resistors") (part "RC0603FR-13180RL"))
    )
    (comp (ref "R172")
      (value "180")
      (footprint "0603")
      (description "YAGEO 0603 180 ohm")
      (fields
        (field (name "MOUSER PART NUMBER") "603-RC0603JR-070RL")
        (field (name "MANUFACTURER_PART_NUMBER") "RC0603JR-070RL")
      )
      (libsource (lib "Resistors") (part "RC0603FR-13180RL"))
    )
    (comp (ref "R173")
      (value "180")
      (footprint "0603")
      (description "YAGEO 0603 180 ohm")
      (fields
        (field (name "MOUSER PART NUMBER") "603-RC0603JR-070RL")
        (field (name "MANUFACTURER_PART_NUMBER") "RC0603JR-070RL")
      )
      (libsource (lib "Resistors") (part "RC0603FR-13180RL"))
    )
    (comp (ref "R174")
      (value "0R")
      (footprint "0603")
      (description "YAGEO 0603 0 ohm")
      (fields
        (field (name "MOUSER PART NUMBER") "603-RC0603JR-070RL")
        (field (name "MANUFACTURER_PART_NUMBER") "RC0603JR-070RL")
      )
      (libsource (lib "Resistors") (part "RC0603JR-070RL"))
    )
    (comp (ref "R175")
      (value "0R")
      (footprint "0603")
      (description "YAGEO 0603 0 ohm")
      (fields
        (field (name "MOUSER PART NUMBER") "603-RC0603JR-070RL")
        (field (name "MANUFACTURER_PART_NUMBER") "RC0603JR-070RL")
      )
      (libsource (lib "Resistors") (part "RC0603JR-070RL"))
    )
    (comp (ref "R176")
      (value "0R")
      (footprint "0603")
      (description "YAGEO 0603 0 ohm")
      (fields
        (field (name "MOUSER PART NUMBER") "603-RC0603JR-070RL")
        (field (name "MANUFACTURER_PART_NUMBER") "RC0603JR-070RL")
      )
      (libsource (lib "Resistors") (part "RC0603JR-070RL"))
    )
    (comp (ref "R177")
      (value "0R")
      (footprint "0603")
      (description "YAGEO 0603 0 ohm")
      (fields
        (field (name "MOUSER PART NUMBER") "603-RC0603JR-070RL")
        (field (name "MANUFACTURER_PART_NUMBER") "RC0603JR-070RL")
      )
      (libsource (lib "Resistors") (part "RC0603JR-070RL"))
    )
    (comp (ref "R178")
      (value "0R")
      (footprint "0603")
      (description "YAGEO 0603 0 ohm")
      (fields
        (field (name "MOUSER PART NUMBER") "603-RC0603JR-070RL")
        (field (name "MANUFACTURER_PART_NUMBER") "RC0603JR-070RL")
      )
      (libsource (lib "Resistors") (part "RC0603JR-070RL"))
    )
    (comp (ref "R179")
      (value "0R")
      (footprint "0603")
      (description "YAGEO 0603 0 ohm")
      (fields
        (field (name "MOUSER PART NUMBER") "603-RC0603JR-070RL")
        (field (name "MANUFACTURER_PART_NUMBER") "RC0603JR-070RL")
      )
      (libsource (lib "Resistors") (part "RC0603JR-070RL"))
    )
    (comp (ref "R180")
      (value "0R")
      (footprint "0603")
      (description "YAGEO 0603 0 ohm")
      (fields
        (field (name "MOUSER PART NUMBER") "603-RC0603JR-070RL")
        (field (name "MANUFACTURER_PART_NUMBER") "RC0603JR-070RL")
      )
      (libsource (lib "Resistors") (part "RC0603JR-070RL"))
    )
    (comp (ref "R181")
      (value "0R")
      (footprint "0603")
      (description "YAGEO 0603 0 ohm")
      (fields
        (field (name "MOUSER PART NUMBER") "603-RC0603JR-070RL")
        (field (name "MANUFACTURER_PART_NUMBER") "RC0603JR-070RL")
      )
      (libsource (lib "Resistors") (part "RC0603JR-070RL"))
    )
    (comp (ref "R182")
      (value "0R")
      (footprint "0603")
      (description "YAGEO 0603 0 ohm")
      (fields
        (field (name "MOUSER PART NUMBER") "603-RC0603JR-070RL")
        (field (name "MANUFACTURER_PART_NUMBER") "RC0603JR-070RL")
      )
      (libsource (lib "Resistors") (part "RC0603JR-070RL"))
    )
    (comp (ref "R183")
      (value "0R")
      (footprint "0603")
      (description "YAGEO 0603 0 ohm")
      (fields
        (field (name "MOUSER PART NUMBER") "603-RC0603JR-070RL")
        (field (name "MANUFACTURER_PART_NUMBER") "RC0603JR-070RL")
      )
      (libsource (lib "Resistors") (part "RC0603JR-070RL"))
    )
    (comp (ref "R184")
      (value "0R")
      (footprint "0603")
      (description "YAGEO 0603 0 ohm")
      (fields
        (field (name "MOUSER PART NUMBER") "603-RC0603JR-070RL")
        (field (name "MANUFACTURER_PART_NUMBER") "RC0603JR-070RL")
      )
      (libsource (lib "Resistors") (part "RC0603JR-070RL"))
    )
    (comp (ref "R185")
      (value "0R")
      (footprint "0603")
      (description "YAGEO 0603 0 ohm")
      (fields
        (field (name "MOUSER PART NUMBER") "603-RC0603JR-070RL")
        (field (name "MANUFACTURER_PART_NUMBER") "RC0603JR-070RL")
      )
      (libsource (lib "Resistors") (part "RC0603JR-070RL"))
    )
    (comp (ref "R186")
      (value "0R")
      (footprint "0603")
      (description "YAGEO 0603 0 ohm")
      (fields
        (field (name "MOUSER PART NUMBER") "603-RC0603JR-070RL")
        (field (name "MANUFACTURER_PART_NUMBER") "RC0603JR-070RL")
      )
      (libsource (lib "Resistors") (part "RC0603JR-070RL"))
    )
    (comp (ref "R187")
      (value "0R")
      (footprint "0603")
      (description "YAGEO 0603 0 ohm")
      (fields
        (field (name "MOUSER PART NUMBER") "603-RC0603JR-070RL")
        (field (name "MANUFACTURER_PART_NUMBER") "RC0603JR-070RL")
      )
      (libsource (lib "Resistors") (part "RC0603JR-070RL"))
    )
    (comp (ref "R188")
      (value "0R")
      (footprint "0603")
      (description "YAGEO 0603 0 ohm")
      (fields
        (field (name "MOUSER PART NUMBER") "603-RC0603JR-070RL")
        (field (name "MANUFACTURER_PART_NUMBER") "RC0603JR-070RL")
      )
      (libsource (lib "Resistors") (part "RC0603JR-070RL"))
    )
    (comp (ref "R189")
      (value "0R")
      (footprint "0603")
      (description "YAGEO 0603 0 ohm")
      (fields
        (field (name "MOUSER PART NUMBER") "603-RC0603JR-070RL")
        (field (name "MANUFACTURER_PART_NUMBER") "RC0603JR-070RL")
      )
      (libsource (lib "Resistors") (part "RC0603JR-070RL"))
    )
    (comp (ref "R190")
      (value "0R")
      (footprint "0603")
      (description "YAGEO 0603 0 ohm")
      (fields
        (field (name "MOUSER PART NUMBER") "603-RC0603JR-070RL")
        (field (name "MANUFACTURER_PART_NUMBER") "RC0603JR-070RL")
      )
      (libsource (lib "Resistors") (part "RC0603JR-070RL"))
    )
    (comp (ref "R191")
      (value "0R")
      (footprint "0603")
      (description "YAGEO 0603 0 ohm")
      (fields
        (field (name "MOUSER PART NUMBER") "603-RC0603JR-070RL")
        (field (name "MANUFACTURER_PART_NUMBER") "RC0603JR-070RL")
      )
      (libsource (lib "Resistors") (part "RC0603JR-070RL"))
    )
    (comp (ref "R192")
      (value "180")
      (footprint "0603")
      (description "YAGEO 0603 180 ohm")
      (fields
        (field (name "MOUSER PART NUMBER") "603-RC0603JR-070RL")
        (field (name "MANUFACTURER_PART_NUMBER") "RC0603JR-070RL")
      )
      (libsource (lib "Resistors") (part "RC0603FR-13180RL"))
    )
    (comp (ref "R193")
      (value "180")
      (footprint "0603")
      (description "YAGEO 0603 180 ohm")
      (fields
        (field (name "MOUSER PART NUMBER") "603-RC0603JR-070RL")
        (field (name "MANUFACTURER_PART_NUMBER") "RC0603JR-070RL")
      )
      (libsource (lib "Resistors") (part "RC0603FR-13180RL"))
    )
    (comp (ref "R194")
      (value "180")
      (footprint "0603")
      (description "YAGEO 0603 180 ohm")
      (fields
        (field (name "MOUSER PART NUMBER") "603-RC0603JR-070RL")
        (field (name "MANUFACTURER_PART_NUMBER") "RC0603JR-070RL")
      )
      (libsource (lib "Resistors") (part "RC0603FR-13180RL"))
    )
    (comp (ref "R195")
      (value "180")
      (footprint "0603")
      (description "YAGEO 0603 180 ohm")
      (fields
        (field (name "MOUSER PART NUMBER") "603-RC0603JR-070RL")
        (field (name "MANUFACTURER_PART_NUMBER") "RC0603JR-070RL")
      )
      (libsource (lib "Resistors") (part "RC0603FR-13180RL"))
    )
    (comp (ref "R196")
      (value "180")
      (footprint "0603")
      (description "YAGEO 0603 180 ohm")
      (fields
        (field (name "MOUSER PART NUMBER") "603-RC0603JR-070RL")
        (field (name "MANUFACTURER_PART_NUMBER") "RC0603JR-070RL")
      )
      (libsource (lib "Resistors") (part "RC0603FR-13180RL"))
    )
    (comp (ref "R197")
      (value "180")
      (footprint "0603")
      (description "YAGEO 0603 180 ohm")
      (fields
        (field (name "MOUSER PART NUMBER") "603-RC0603JR-070RL")
        (field (name "MANUFACTURER_PART_NUMBER") "RC0603JR-070RL")
      )
      (libsource (lib "Resistors") (part "RC0603FR-13180RL"))
    )
    (comp (ref "R198")
      (value "180")
      (footprint "0603")
      (description "YAGEO 0603 180 ohm")
      (fields
        (field (name "MOUSER PART NUMBER") "603-RC0603JR-070RL")
        (field (name "MANUFACTURER_PART_NUMBER") "RC0603JR-070RL")
      )
      (libsource (lib "Resistors") (part "RC0603FR-13180RL"))
    )
    (comp (ref "R199")
      (value "180")
      (footprint "0603")
      (description "YAGEO 0603 180 ohm")
      (fields
        (field (name "MOUSER PART NUMBER") "603-RC0603JR-070RL")
        (field (name "MANUFACTURER_PART_NUMBER") "RC0603JR-070RL")
      )
      (libsource (lib "Resistors") (part "RC0603FR-13180RL"))
    )
    (comp (ref "R200")
      (value "180")
      (footprint "0603")
      (description "YAGEO 0603 180 ohm")
      (fields
        (field (name "MOUSER PART NUMBER") "603-RC0603JR-070RL")
        (field (name "MANUFACTURER_PART_NUMBER") "RC0603JR-070RL")
      )
      (libsource (lib "Resistors") (part "RC0603FR-13180RL"))
    )
    (comp (ref "R201")
      (value "180")
      (footprint "0603")
      (description "YAGEO 0603 180 ohm")
      (fields
        (field (name "MOUSER PART NUMBER") "603-RC0603JR-070RL")
        (field (name "MANUFACTURER_PART_NUMBER") "RC0603JR-070RL")
      )
      (libsource (lib "Resistors") (part "RC0603FR-13180RL"))
    )
    (comp (ref "R202")
      (value "0R")
      (footprint "0603")
      (description "YAGEO 0603 0 ohm")
      (fields
        (field (name "MOUSER PART NUMBER") "603-RC0603JR-070RL")
        (field (name "MANUFACTURER_PART_NUMBER") "RC0603JR-070RL")
      )
      (libsource (lib "Resistors") (part "RC0603JR-070RL"))
    )
    (comp (ref "R203")
      (value "0R")
      (footprint "0603")
      (description "YAGEO 0603 0 ohm")
      (fields
        (field (name "MOUSER PART NUMBER") "603-RC0603JR-070RL")
        (field (name "MANUFACTURER_PART_NUMBER") "RC0603JR-070RL")
      )
      (libsource (lib "Resistors") (part "RC0603JR-070RL"))
    )
    (comp (ref "R204")
      (value "0R")
      (footprint "0603")
      (description "YAGEO 0603 0 ohm")
      (fields
        (field (name "MOUSER PART NUMBER") "603-RC0603JR-070RL")
        (field (name "MANUFACTURER_PART_NUMBER") "RC0603JR-070RL")
      )
      (libsource (lib "Resistors") (part "RC0603JR-070RL"))
    )
    (comp (ref "R205")
      (value "0R")
      (footprint "0603")
      (description "YAGEO 0603 0 ohm")
      (fields
        (field (name "MOUSER PART NUMBER") "603-RC0603JR-070RL")
        (field (name "MANUFACTURER_PART_NUMBER") "RC0603JR-070RL")
      )
      (libsource (lib "Resistors") (part "RC0603JR-070RL"))
    )
    (comp (ref "R206")
      (value "0R")
      (footprint "0603")
      (description "YAGEO 0603 0 ohm")
      (fields
        (field (name "MOUSER PART NUMBER") "603-RC0603JR-070RL")
        (field (name "MANUFACTURER_PART_NUMBER") "RC0603JR-070RL")
      )
      (libsource (lib "Resistors") (part "RC0603JR-070RL"))
    )
    (comp (ref "R207")
      (value "0R")
      (footprint "0603")
      (description "YAGEO 0603 0 ohm")
      (fields
        (field (name "MOUSER PART NUMBER") "603-RC0603JR-070RL")
        (field (name "MANUFACTURER_PART_NUMBER") "RC0603JR-070RL")
      )
      (libsource (lib "Resistors") (part "RC0603JR-070RL"))
    )
    (comp (ref "R208")
      (value "0R")
      (footprint "0603")
      (description "YAGEO 0603 0 ohm")
      (fields
        (field (name "MOUSER PART NUMBER") "603-RC0603JR-070RL")
        (field (name "MANUFACTURER_PART_NUMBER") "RC0603JR-070RL")
      )
      (libsource (lib "Resistors") (part "RC0603JR-070RL"))
    )
    (comp (ref "R209")
      (value "0R")
      (footprint "0603")
      (description "YAGEO 0603 0 ohm")
      (fields
        (field (name "MOUSER PART NUMBER") "603-RC0603JR-070RL")
        (field (name "MANUFACTURER_PART_NUMBER") "RC0603JR-070RL")
      )
      (libsource (lib "Resistors") (part "RC0603JR-070RL"))
    )
    (comp (ref "R210")
      (value "0R")
      (footprint "0603")
      (description "YAGEO 0603 0 ohm")
      (fields
        (field (name "MOUSER PART NUMBER") "603-RC0603JR-070RL")
        (field (name "MANUFACTURER_PART_NUMBER") "RC0603JR-070RL")
      )
      (libsource (lib "Resistors") (part "RC0603JR-070RL"))
    )
    (comp (ref "R211")
      (value "0R")
      (footprint "0603")
      (description "YAGEO 0603 0 ohm")
      (fields
        (field (name "MOUSER PART NUMBER") "603-RC0603JR-070RL")
        (field (name "MANUFACTURER_PART_NUMBER") "RC0603JR-070RL")
      )
      (libsource (lib "Resistors") (part "RC0603JR-070RL"))
    )
    (comp (ref "R212")
      (value "0R")
      (footprint "0603")
      (description "YAGEO 0603 0 ohm")
      (fields
        (field (name "MOUSER PART NUMBER") "603-RC0603JR-070RL")
        (field (name "MANUFACTURER_PART_NUMBER") "RC0603JR-070RL")
      )
      (libsource (lib "Resistors") (part "RC0603JR-070RL"))
    )
    (comp (ref "R213")
      (value "0R")
      (footprint "0603")
      (description "YAGEO 0603 0 ohm")
      (fields
        (field (name "MOUSER PART NUMBER") "603-RC0603JR-070RL")
        (field (name "MANUFACTURER_PART_NUMBER") "RC0603JR-070RL")
      )
      (libsource (lib "Resistors") (part "RC0603JR-070RL"))
    )
    (comp (ref "R214")
      (value "0R")
      (footprint "0603")
      (description "YAGEO 0603 0 ohm")
      (fields
        (field (name "MOUSER PART NUMBER") "603-RC0603JR-070RL")
        (field (name "MANUFACTURER_PART_NUMBER") "RC0603JR-070RL")
      )
      (libsource (lib "Resistors") (part "RC0603JR-070RL"))
    )
    (comp (ref "R215")
      (value "0R")
      (footprint "0603")
      (description "YAGEO 0603 0 ohm")
      (fields
        (field (name "MOUSER PART NUMBER") "603-RC0603JR-070RL")
        (field (name "MANUFACTURER_PART_NUMBER") "RC0603JR-070RL")
      )
      (libsource (lib "Resistors") (part "RC0603JR-070RL"))
    )
    (comp (ref "R216")
      (value "0R")
      (footprint "0603")
      (description "YAGEO 0603 0 ohm")
      (fields
        (field (name "MOUSER PART NUMBER") "603-RC0603JR-070RL")
        (field (name "MANUFACTURER_PART_NUMBER") "RC0603JR-070RL")
      )
      (libsource (lib "Resistors") (part "RC0603JR-070RL"))
    )
    (comp (ref "R217")
      (value "0R")
      (footprint "0603")
      (description "YAGEO 0603 0 ohm")
      (fields
        (field (name "MOUSER PART NUMBER") "603-RC0603JR-070RL")
        (field (name "MANUFACTURER_PART_NUMBER") "RC0603JR-070RL")
      )
      (libsource (lib "Resistors") (part "RC0603JR-070RL"))
    )
    (comp (ref "R218")
      (value "0R")
      (footprint "0603")
      (description "YAGEO 0603 0 ohm")
      (fields
        (field (name "MOUSER PART NUMBER") "603-RC0603JR-070RL")
        (field (name "MANUFACTURER_PART_NUMBER") "RC0603JR-070RL")
      )
      (libsource (lib "Resistors") (part "RC0603JR-070RL"))
    )
    (comp (ref "R219")
      (value "0R")
      (footprint "0603")
      (description "YAGEO 0603 0 ohm")
      (fields
        (field (name "MOUSER PART NUMBER") "603-RC0603JR-070RL")
        (field (name "MANUFACTURER_PART_NUMBER") "RC0603JR-070RL")
      )
      (libsource (lib "Resistors") (part "RC0603JR-070RL"))
    )
    (comp (ref "R220")
      (value "0R")
      (footprint "0603")
      (description "YAGEO 0603 0 ohm")
      (fields
        (field (name "MOUSER PART NUMBER") "603-RC0603JR-070RL")
        (field (name "MANUFACTURER_PART_NUMBER") "RC0603JR-070RL")
      )
      (libsource (lib "Resistors") (part "RC0603JR-070RL"))
    )
    (comp (ref "R221")
      (value "0R")
      (footprint "0603")
      (description "YAGEO 0603 0 ohm")
      (fields
        (field (name "MOUSER PART NUMBER") "603-RC0603JR-070RL")
        (field (name "MANUFACTURER_PART_NUMBER") "RC0603JR-070RL")
      )
      (libsource (lib "Resistors") (part "RC0603JR-070RL"))
    )
    (comp (ref "R222")
      (value "0R")
      (footprint "0603")
      (description "YAGEO 0603 0 ohm")
      (fields
        (field (name "MOUSER PART NUMBER") "603-RC0603JR-070RL")
        (field (name "MANUFACTURER_PART_NUMBER") "RC0603JR-070RL")
      )
      (libsource (lib "Resistors") (part "RC0603JR-070RL"))
    )
    (comp (ref "R223")
      (value "0R")
      (footprint "0603")
      (description "YAGEO 0603 0 ohm")
      (fields
        (field (name "MOUSER PART NUMBER") "603-RC0603JR-070RL")
        (field (name "MANUFACTURER_PART_NUMBER") "RC0603JR-070RL")
      )
      (libsource (lib "Resistors") (part "RC0603JR-070RL"))
    )
    (comp (ref "R224")
      (value "0R")
      (footprint "0603")
      (description "YAGEO 0603 0 ohm")
      (fields
        (field (name "MOUSER PART NUMBER") "603-RC0603JR-070RL")
        (field (name "MANUFACTURER_PART_NUMBER") "RC0603JR-070RL")
      )
      (libsource (lib "Resistors") (part "RC0603JR-070RL"))
    )
    (comp (ref "R225")
      (value "0R")
      (footprint "0603")
      (description "YAGEO 0603 0 ohm")
      (fields
        (field (name "MOUSER PART NUMBER") "603-RC0603JR-070RL")
        (field (name "MANUFACTURER_PART_NUMBER") "RC0603JR-070RL")
      )
      (libsource (lib "Resistors") (part "RC0603JR-070RL"))
    )
    (comp (ref "R226")
      (value "0R")
      (footprint "0603")
      (description "YAGEO 0603 0 ohm")
      (fields
        (field (name "MOUSER PART NUMBER") "603-RC0603JR-070RL")
        (field (name "MANUFACTURER_PART_NUMBER") "RC0603JR-070RL")
      )
      (libsource (lib "Resistors") (part "RC0603JR-070RL"))
    )
    (comp (ref "R227")
      (value "0R")
      (footprint "0603")
      (description "YAGEO 0603 0 ohm")
      (fields
        (field (name "MOUSER PART NUMBER") "603-RC0603JR-070RL")
        (field (name "MANUFACTURER_PART_NUMBER") "RC0603JR-070RL")
      )
      (libsource (lib "Resistors") (part "RC0603JR-070RL"))
    )
    (comp (ref "TitleBlock_2") (value "TitleBlock") (libsource (lib "Misc") (part "TitleBlock")))
    (comp (ref "TP8")
      (value "TP")
      (footprint "TP")
      (fields
        (field (name "MANUFACTURER") "Samtec")
        (field (name "MANUFACTURER PART NUMBER") "TST-105-01-G-D")
      )
      (libsource (lib "Misc") (part "TP"))
    )
    (comp (ref "TP9")
      (value "TP")
      (footprint "TP")
      (fields
        (field (name "MANUFACTURER") "Samtec")
        (field (name "MANUFACTURER PART NUMBER") "TST-105-01-G-D")
      )
      (libsource (lib "") (part "TP_1"))
    )
    (comp (ref "TP10")
      (value "TP")
      (footprint "TP")
      (fields
        (field (name "MANUFACTURER") "Samtec")
        (field (name "MANUFACTURER PART NUMBER") "TST-105-01-G-D")
      )
      (libsource (lib "Misc") (part "TP"))
    )
    (comp (ref "TP11")
      (value "TP")
      (footprint "TP")
      (fields
        (field (name "MANUFACTURER") "Samtec")
        (field (name "MANUFACTURER PART NUMBER") "TST-105-01-G-D")
      )
      (libsource (lib "") (part "TP_1"))
    )
    (comp (ref "U1")
      (value "SN74ABT240ADBR")
      (footprint "SOP65P780X200-20N")
      (description "Octal Buffers/Drivers With 3-State Outputs")
      (fields (field (name "MOUSER PART NUMBER") "595-SN74ABT240ADBR"))
      (libsource (lib "Logic") (part "SN74ABT240ADBR"))
    )
    (comp (ref "U2")
      (value "SN74AC04PWR")
      (footprint "SOP65P640X120-14N")
      (description "Hex Inverters")
      (fields (field (name "MOUSER PART NUMBER") "595-SN74AC04PWR"))
      (libsource (lib "Logic") (part "SN74AC04PWR"))
    )
    (comp (ref "U3")
      (value "SN74AC04PWR")
      (footprint "SOP65P640X120-14N")
      (description "Hex Inverters")
      (fields (field (name "MOUSER PART NUMBER") "595-SN74AC04PWR"))
      (libsource (lib "Logic") (part "SN74AC04PWR"))
    )
    (comp (ref "U4")
      (value "SN74ABT240ADBR")
      (footprint "SOP65P780X200-20N")
      (description "Octal Buffers/Drivers With 3-State Outputs")
      (fields (field (name "MOUSER PART NUMBER") "595-SN74ABT240ADBR"))
      (libsource (lib "Logic") (part "SN74ABT240ADBR"))
    )
    (comp (ref "U5")
      (value "SN74AC04PWR")
      (footprint "SOP65P640X120-14N")
      (description "Hex Inverters")
      (fields (field (name "MOUSER PART NUMBER") "595-SN74AC04PWR"))
      (libsource (lib "Logic") (part "SN74AC04PWR"))
    )
    (comp (ref "U6")
      (value "SN74AC04PWR")
      (footprint "SOP65P640X120-14N")
      (description "Hex Inverters")
      (fields (field (name "MOUSER PART NUMBER") "595-SN74AC04PWR"))
      (libsource (lib "Logic") (part "SN74AC04PWR"))
    )
  )
  (nets
    (net (code "1") (name "+3.3") (class "Default")
      (node (ref "R150") (pin "1") (pinfunction "1_1") (pintype "passive"))
    )
    (net (code "2") (name "+5") (class "Default")
      (node (ref "R116") (pin "2") (pinfunction "2_2") (pintype "passive"))
      (node (ref "R117") (pin "2") (pinfunction "2_2") (pintype "passive"))
      (node (ref "R118") (pin "2") (pinfunction "2_2") (pintype "passive"))
      (node (ref "R119") (pin "2") (pinfunction "2_2") (pintype "passive"))
      (node (ref "R120") (pin "2") (pinfunction "2_2") (pintype "passive"))
      (node (ref "R121") (pin "2") (pinfunction "2_2") (pintype "passive"))
      (node (ref "R122") (pin "2") (pinfunction "2_2") (pintype "passive"))
      (node (ref "R123") (pin "2") (pinfunction "2_2") (pintype "passive"))
      (node (ref "R124") (pin "2") (pinfunction "2_2") (pintype "passive"))
      (node (ref "R125") (pin "2") (pinfunction "2_2") (pintype "passive"))
      (node (ref "R126") (pin "2") (pinfunction "2_2") (pintype "passive"))
      (node (ref "R127") (pin "2") (pinfunction "2_2") (pintype "passive"))
      (node (ref "R128") (pin "2") (pinfunction "2_2") (pintype "passive"))
      (node (ref "R129") (pin "2") (pinfunction "2_2") (pintype "passive"))
      (node (ref "R130") (pin "2") (pinfunction "2_2") (pintype "passive"))
      (node (ref "R131") (pin "1") (pinfunction "1_1") (pintype "passive"))
      (node (ref "R132") (pin "2") (pinfunction "2_2") (pintype "passive"))
      (node (ref "R133") (pin "2") (pinfunction "2_2") (pintype "passive"))
      (node (ref "R134") (pin "2") (pinfunction "2_2") (pintype "passive"))
      (node (ref "R135") (pin "2") (pinfunction "2_2") (pintype "passive"))
      (node (ref "R136") (pin "2") (pinfunction "2_2") (pintype "passive"))
      (node (ref "R137") (pin "2") (pinfunction "2_2") (pintype "passive"))
      (node (ref "R138") (pin "2") (pinfunction "2_2") (pintype "passive"))
      (node (ref "R139") (pin "2") (pinfunction "2_2") (pintype "passive"))
      (node (ref "R140") (pin "2") (pinfunction "2_2") (pintype "passive"))
      (node (ref "R141") (pin "2") (pinfunction "2_2") (pintype "passive"))
      (node (ref "R149") (pin "2") (pinfunction "2_2") (pintype "passive"))
      (node (ref "R153") (pin "2") (pinfunction "2_2") (pintype "passive"))
      (node (ref "R154") (pin "2") (pinfunction "2_2") (pintype "passive"))
      (node (ref "R155") (pin "2") (pinfunction "2_2") (pintype "passive"))
      (node (ref "R156") (pin "2") (pinfunction "2_2") (pintype "passive"))
      (node (ref "R157") (pin "2") (pinfunction "2_2") (pintype "passive"))
      (node (ref "R158") (pin "2") (pinfunction "2_2") (pintype "passive"))
      (node (ref "R159") (pin "2") (pinfunction "2_2") (pintype "passive"))
      (node (ref "R160") (pin "2") (pinfunction "2_2") (pintype "passive"))
      (node (ref "R161") (pin "2") (pinfunction "2_2") (pintype "passive"))
      (node (ref "R162") (pin "2") (pinfunction "2_2") (pintype "passive"))
      (node (ref "R166") (pin "2") (pinfunction "2_2") (pintype "passive"))
      (node (ref "R167") (pin "2") (pinfunction "2_2") (pintype "passive"))
      (node (ref "R168") (pin "2") (pinfunction "2_2") (pintype "passive"))
      (node (ref "R169") (pin "2") (pinfunction "2_2") (pintype "passive"))
      (node (ref "R170") (pin "2") (pinfunction "2_2") (pintype "passive"))
      (node (ref "R171") (pin "2") (pinfunction "2_2") (pintype "passive"))
      (node (ref "R172") (pin "2") (pinfunction "2_2") (pintype "passive"))
      (node (ref "R173") (pin "2") (pinfunction "2_2") (pintype "passive"))
      (node (ref "R192") (pin "2") (pinfunction "2_2") (pintype "passive"))
      (node (ref "R193") (pin "2") (pinfunction "2_2") (pintype "passive"))
      (node (ref "R194") (pin "2") (pinfunction "2_2") (pintype "passive"))
      (node (ref "R195") (pin "2") (pinfunction "2_2") (pintype "passive"))
      (node (ref "R196") (pin "2") (pinfunction "2_2") (pintype "passive"))
      (node (ref "R197") (pin "2") (pinfunction "2_2") (pintype "passive"))
      (node (ref "R198") (pin "2") (pinfunction "2_2") (pintype "passive"))
      (node (ref "R199") (pin "2") (pinfunction "2_2") (pintype "passive"))
      (node (ref "R200") (pin "2") (pinfunction "2_2") (pintype "passive"))
      (node (ref "R201") (pin "2") (pinfunction "2_2") (pintype "passive"))
      (node (ref "U1") (pin "20") (pinfunction "VCC_20") (pintype "passive"))
      (node (ref "U2") (pin "14") (pinfunction "VCC_14") (pintype "passive"))
      (node (ref "U3") (pin "14") (pinfunction "VCC_14") (pintype "passive"))
      (node (ref "U4") (pin "20") (pinfunction "VCC_20") (pintype "passive"))
      (node (ref "U5") (pin "14") (pinfunction "VCC_14") (pintype "passive"))
      (node (ref "U6") (pin "14") (pinfunction "VCC_14") (pintype "passive"))
    )
    (net (code "3") (name "/CPU_CS") (class "Default")
      (node (ref "R142") (pin "1") (pinfunction "1_1") (pintype "passive"))
    )
    (net (code "4") (name "/CPU_D0") (class "Default")
      (node (ref "U1") (pin "2") (pinfunction "1A1_2") (pintype "passive"))
    )
    (net (code "5") (name "/CPU_D1") (class "Default")
      (node (ref "U1") (pin "4") (pinfunction "1A2_4") (pintype "passive"))
    )
    (net (code "6") (name "/CPU_D2") (class "Default")
      (node (ref "U1") (pin "6") (pinfunction "1A3_6") (pintype "passive"))
    )
    (net (code "7") (name "/CPU_D3") (class "Default")
      (node (ref "U1") (pin "8") (pinfunction "1A4_8") (pintype "passive"))
    )
    (net (code "8") (name "/CPU_D4") (class "Default")
      (node (ref "U1") (pin "11") (pinfunction "2A1_11") (pintype "passive"))
    )
    (net (code "9") (name "/CPU_D5") (class "Default")
      (node (ref "U1") (pin "13") (pinfunction "2A2_13") (pintype "passive"))
    )
    (net (code "10") (name "/CPU_D6") (class "Default")
      (node (ref "U1") (pin "15") (pinfunction "2A3_15") (pintype "passive"))
    )
    (net (code "11") (name "/CPU_D7") (class "Default")
      (node (ref "U1") (pin "17") (pinfunction "2A4_17") (pintype "passive"))
    )
    (net (code "12") (name "/CPU_LED_Read") (class "Default")
      (node (ref "LED17") (pin "1") (pinfunction "K_1") (pintype "passive"))
      (node (ref "U2") (pin "8") (pinfunction "4Y_8") (pintype "passive"))
    )
    (net (code "13") (name "/CPU_LED_Write") (class "Default")
      (node (ref "LED26") (pin "1") (pinfunction "K_1") (pintype "passive"))
      (node (ref "U2") (pin "12") (pinfunction "6Y_12") (pintype "passive"))
    )
    (net (code "14") (name "/CPU_Reset") (class "Default")
      (node (ref "R145") (pin "1") (pinfunction "1_1") (pintype "passive"))
    )
    (net (code "15") (name "/CPU_RnW") (class "Default")
      (node (ref "R163") (pin "1") (pinfunction "1_1") (pintype "passive"))
      (node (ref "R164") (pin "1") (pinfunction "1_1") (pintype "passive"))
    )
    (net (code "16") (name "/CPU_nInt") (class "Default")
      (node (ref "R143") (pin "1") (pinfunction "1_1") (pintype "passive"))
    )
    (net (code "17") (name "/I2C_LED_SDA") (class "Default")
      (node (ref "LED9") (pin "1") (pinfunction "K_1") (pintype "passive"))
      (node (ref "R203") (pin "2") (pinfunction "2_2") (pintype "passive"))
    )
    (net (code "18") (name "/I2C_LED_SDC") (class "Default")
      (node (ref "LED8") (pin "1") (pinfunction "K_1") (pintype "passive"))
      (node (ref "R191") (pin "2") (pinfunction "2_2") (pintype "passive"))
    )
    (net (code "19") (name "/I2C_SDA") (class "Default")
      (node (ref "R202") (pin "1") (pinfunction "1_1") (pintype "passive"))
    )
    (net (code "20") (name "/I2C_SDC") (class "Default")
      (node (ref "R190") (pin "1") (pinfunction "1_1") (pintype "passive"))
    )
    (net (code "21") (name "/Invert_Read") (class "Default")
      (node (ref "R165") (pin "1") (pinfunction "1_1") (pintype "passive"))
      (node (ref "U2") (pin "10") (pinfunction "5Y_10") (pintype "passive"))
    )
    (net (code "22") (name "/LCD1_CnD") (class "Default")
      (node (ref "R174") (pin "1") (pinfunction "1_1") (pintype "passive"))
      (node (ref "R204") (pin "1") (pinfunction "1_1") (pintype "passive"))
    )
    (net (code "23") (name "/LCD1_Cntrl_Extra") (class "Default")
      (node (ref "LED38") (pin "1") (pinfunction "K_1") (pintype "passive"))
      (node (ref "R211") (pin "2") (pinfunction "2_2") (pintype "passive"))
    )
    (net (code "24") (name "/LCD1_Cntrl_FS") (class "Default")
      (node (ref "LED37") (pin "1") (pinfunction "K_1") (pintype "passive"))
      (node (ref "R209") (pin "2") (pinfunction "2_2") (pintype "passive"))
    )
    (net (code "25") (name "/LCD1_Extra") (class "Default")
      (node (ref "R210") (pin "1") (pinfunction "1_1") (pintype "passive"))
    )
    (net (code "26") (name "/LCD1_FS") (class "Default")
      (node (ref "R208") (pin "1") (pinfunction "1_1") (pintype "passive"))
    )
    (net (code "27") (name "/LCD1_Instruction") (class "Default")
      (node (ref "LED29") (pin "1") (pinfunction "K_1") (pintype "passive"))
      (node (ref "R205") (pin "2") (pinfunction "2_2") (pintype "passive"))
    )
    (net (code "28") (name "/LCD1_Mid") (class "Default")
      (node (ref "R187") (pin "1") (pinfunction "1_1") (pintype "passive"))
      (node (ref "R206") (pin "1") (pinfunction "1_1") (pintype "passive"))
    )
    (net (code "29") (name "/LCD1_Mid_Left") (class "Default")
      (node (ref "LED35") (pin "1") (pinfunction "K_1") (pintype "passive"))
      (node (ref "R207") (pin "2") (pinfunction "2_2") (pintype "passive"))
    )
    (net (code "30") (name "/LCD1_Reset") (class "Default")
      (node (ref "R179") (pin "1") (pinfunction "1_1") (pintype "passive"))
    )
    (net (code "31") (name "/LCD1_nCE") (class "Default")
      (node (ref "R182") (pin "1") (pinfunction "1_1") (pintype "passive"))
    )
    (net (code "32") (name "/LCD1_nRD") (class "Default")
      (node (ref "R175") (pin "1") (pinfunction "1_1") (pintype "passive"))
    )
    (net (code "33") (name "/LCD1_nWR") (class "Default")
      (node (ref "R176") (pin "1") (pinfunction "1_1") (pintype "passive"))
    )
    (net (code "34") (name "/LCD2_DnI") (class "Default")
      (node (ref "R218") (pin "1") (pinfunction "1_1") (pintype "passive"))
      (node (ref "R219") (pin "1") (pinfunction "1_1") (pintype "passive"))
    )
    (net (code "35") (name "/LCD2_DnI_Instruction") (class "Default")
      (node (ref "R217") (pin "1") (pinfunction "1_1") (pintype "passive"))
      (node (ref "U6") (pin "2") (pinfunction "1Y_2") (pintype "passive"))
    )
    (net (code "36") (name "/LCD2_Enable") (class "Default")
      (node (ref "R220") (pin "1") (pinfunction "1_1") (pintype "passive"))
    )
    (net (code "37") (name "/LCD2_Enable_LEDG") (class "Default")
      (node (ref "LED54") (pin "1") (pinfunction "K_1") (pintype "passive"))
      (node (ref "U6") (pin "4") (pinfunction "2Y_4") (pintype "passive"))
    )
    (net (code "38") (name "/LCD2_Extra_1") (class "Default")
      (node (ref "R222") (pin "1") (pinfunction "1_1") (pintype "passive"))
    )
    (net (code "39") (name "/LCD2_Extra_1_LEDG") (class "Default")
      (node (ref "LED55") (pin "1") (pinfunction "K_1") (pintype "passive"))
      (node (ref "U6") (pin "6") (pinfunction "3Y_6") (pintype "passive"))
    )
    (net (code "40") (name "/LCD2_Extra_2") (class "Default")
      (node (ref "R223") (pin "1") (pinfunction "1_1") (pintype "passive"))
    )
    (net (code "41") (name "/LCD2_Extra_2_LEDG") (class "Default")
      (node (ref "LED56") (pin "1") (pinfunction "K_1") (pintype "passive"))
      (node (ref "U6") (pin "8") (pinfunction "4Y_8") (pintype "passive"))
    )
    (net (code "42") (name "/LCD2_Reset") (class "Default")
      (node (ref "R216") (pin "1") (pinfunction "1_1") (pintype "passive"))
    )
    (net (code "43") (name "/LCD2_RnW") (class "Default")
      (node (ref "R212") (pin "1") (pinfunction "1_1") (pintype "passive"))
      (node (ref "R221") (pin "1") (pinfunction "1_1") (pintype "passive"))
    )
    (net (code "44") (name "/LCD2_RnW_Read") (class "Default")
      (node (ref "LED52") (pin "1") (pinfunction "K_1") (pintype "passive"))
      (node (ref "R213") (pin "2") (pinfunction "2_2") (pintype "passive"))
    )
    (net (code "45") (name "/LCD2_nCS1") (class "Default")
      (node (ref "R214") (pin "1") (pinfunction "1_1") (pintype "passive"))
    )
    (net (code "46") (name "/LCD2_nCS2") (class "Default")
      (node (ref "R215") (pin "1") (pinfunction "1_1") (pintype "passive"))
    )
    (net (code "47") (name "/LCD_D0") (class "Default")
      (node (ref "U4") (pin "2") (pinfunction "1A1_2") (pintype "passive"))
    )
    (net (code "48") (name "/LCD_D1") (class "Default")
      (node (ref "U4") (pin "4") (pinfunction "1A2_4") (pintype "passive"))
    )
    (net (code "49") (name "/LCD_D2") (class "Default")
      (node (ref "U4") (pin "6") (pinfunction "1A3_6") (pintype "passive"))
    )
    (net (code "50") (name "/LCD_D3") (class "Default")
      (node (ref "U4") (pin "8") (pinfunction "1A4_8") (pintype "passive"))
    )
    (net (code "51") (name "/LCD_D4") (class "Default")
      (node (ref "U4") (pin "11") (pinfunction "2A1_11") (pintype "passive"))
    )
    (net (code "52") (name "/LCD_D5") (class "Default")
      (node (ref "U4") (pin "13") (pinfunction "2A2_13") (pintype "passive"))
    )
    (net (code "53") (name "/LCD_D6") (class "Default")
      (node (ref "U4") (pin "15") (pinfunction "2A3_15") (pintype "passive"))
    )
    (net (code "54") (name "/LCD_D7") (class "Default")
      (node (ref "U4") (pin "17") (pinfunction "2A4_17") (pintype "passive"))
    )
    (net (code "55") (name "/LED1_Ser_Data_0") (class "Default")
      (node (ref "LED5") (pin "1") (pinfunction "K_1") (pintype "passive"))
      (node (ref "U2") (pin "2") (pinfunction "1Y_2") (pintype "passive"))
    )
    (net (code "56") (name "/LED1_Ser_Data_1") (class "Default")
      (node (ref "LED6") (pin "1") (pinfunction "K_1") (pintype "passive"))
      (node (ref "U2") (pin "4") (pinfunction "2Y_4") (pintype "passive"))
    )
    (net (code "57") (name "/LED1_Ser_Data_2") (class "Default")
      (node (ref "LED7") (pin "1") (pinfunction "K_1") (pintype "passive"))
      (node (ref "U2") (pin "6") (pinfunction "3Y_6") (pintype "passive"))
    )
    (net (code "58") (name "/RCLK") (class "Default")
      (node (ref "R177") (pin "1") (pinfunction "1_1") (pintype "passive"))
    )
    (net (code "59") (name "/SCLK") (class "Default")
      (node (ref "R180") (pin "1") (pinfunction "1_1") (pintype "passive"))
    )
    (net (code "60") (name "/SCLR") (class "Default")
      (node (ref "R146") (pin "1") (pinfunction "1_1") (pintype "passive"))
    )
    (net (code "61") (name "/SER_Data_0") (class "Default")
      (node (ref "R148") (pin "1") (pinfunction "1_1") (pintype "passive"))
    )
    (net (code "62") (name "/SER_Data_1") (class "Default")
      (node (ref "R151") (pin "1") (pinfunction "1_1") (pintype "passive"))
    )
    (net (code "63") (name "/SER_Data_2") (class "Default")
      (node (ref "R152") (pin "1") (pinfunction "1_1") (pintype "passive"))
    )
    (net (code "64") (name "/SPI_LED_MISO") (class "Default")
      (node (ref "LED11") (pin "1") (pinfunction "K_1") (pintype "passive"))
      (node (ref "R186") (pin "2") (pinfunction "2_2") (pintype "passive"))
    )
    (net (code "65") (name "/SPI_LED_MOSI") (class "Default")
      (node (ref "LED12") (pin "1") (pinfunction "K_1") (pintype "passive"))
      (node (ref "R189") (pin "2") (pinfunction "2_2") (pintype "passive"))
    )
    (net (code "66") (name "/SPI_LED_SCK") (class "Default")
      (node (ref "LED10") (pin "1") (pinfunction "K_1") (pintype "passive"))
      (node (ref "R184") (pin "2") (pinfunction "2_2") (pintype "passive"))
    )
    (net (code "67") (name "/SPI_MISO") (class "Default")
      (node (ref "R185") (pin "1") (pinfunction "1_1") (pintype "passive"))
    )
    (net (code "68") (name "/SPI_MOSI") (class "Default")
      (node (ref "R188") (pin "1") (pinfunction "1_1") (pintype "passive"))
    )
    (net (code "69") (name "/SPI_SCK") (class "Default")
      (node (ref "R183") (pin "1") (pinfunction "1_1") (pintype "passive"))
    )
    (net (code "70") (name "/SPI_SS") (class "Default")
      (node (ref "R147") (pin "1") (pinfunction "1_1") (pintype "passive"))
    )
    (net (code "71") (name "/Ser_RCLK") (class "Default")
      (node (ref "LED1") (pin "1") (pinfunction "K_1") (pintype "passive"))
      (node (ref "R178") (pin "2") (pinfunction "2_2") (pintype "passive"))
    )
    (net (code "72") (name "/Ser_SCLK") (class "Default")
      (node (ref "LED2") (pin "1") (pinfunction "K_1") (pintype "passive"))
      (node (ref "R181") (pin "2") (pinfunction "2_2") (pintype "passive"))
    )
    (net (code "73") (name "/nOE") (class "Default")
      (node (ref "R144") (pin "1") (pinfunction "1_1") (pintype "passive"))
    )
    (net (code "74") (name "GND") (class "Default")
      (node (ref "LED27") (pin "1") (pinfunction "K_1") (pintype "passive"))
      (node (ref "LED28") (pin "1") (pinfunction "K_1") (pintype "passive"))
      (node (ref "U1") (pin "1") (pinfunction "~{1}OE_1") (pintype "passive"))
      (node (ref "U1") (pin "10") (pinfunction "GND_10") (pintype "passive"))
      (node (ref "U1") (pin "19") (pinfunction "~{2}OE_19") (pintype "passive"))
      (node (ref "U2") (pin "7") (pinfunction "GND_7") (pintype "passive"))
      (node (ref "U3") (pin "7") (pinfunction "GND_7") (pintype "passive"))
      (node (ref "U4") (pin "1") (pinfunction "~{1}OE_1") (pintype "passive"))
      (node (ref "U4") (pin "10") (pinfunction "GND_10") (pintype "passive"))
      (node (ref "U4") (pin "19") (pinfunction "~{2}OE_19") (pintype "passive"))
      (node (ref "U5") (pin "7") (pinfunction "GND_7") (pintype "passive"))
      (node (ref "U6") (pin "7") (pinfunction "GND_7") (pintype "passive"))
    )
    (net (code "75") (name "Net-(LED1-A)") (class "Default")
      (node (ref "LED1") (pin "2") (pinfunction "A_2") (pintype "passive"))
      (node (ref "R116") (pin "1") (pinfunction "1_1") (pintype "passive"))
    )
    (net (code "76") (name "Net-(LED2-A)") (class "Default")
      (node (ref "LED2") (pin "2") (pinfunction "A_2") (pintype "passive"))
      (node (ref "R117") (pin "1") (pinfunction "1_1") (pintype "passive"))
    )
    (net (code "77") (name "Net-(LED3-A)") (class "Default")
      (node (ref "LED3") (pin "2") (pinfunction "A_2") (pintype "passive"))
      (node (ref "R118") (pin "1") (pinfunction "1_1") (pintype "passive"))
    )
    (net (code "78") (name "Net-(LED3-K)") (class "Default")
      (node (ref "LED3") (pin "1") (pinfunction "K_1") (pintype "passive"))
      (node (ref "R144") (pin "2") (pinfunction "2_2") (pintype "passive"))
    )
    (net (code "79") (name "Net-(LED4-A)") (class "Default")
      (node (ref "LED4") (pin "2") (pinfunction "A_2") (pintype "passive"))
      (node (ref "R119") (pin "1") (pinfunction "1_1") (pintype "passive"))
    )
    (net (code "80") (name "Net-(LED4-K)") (class "Default")
      (node (ref "LED4") (pin "1") (pinfunction "K_1") (pintype "passive"))
      (node (ref "R146") (pin "2") (pinfunction "2_2") (pintype "passive"))
    )
    (net (code "81") (name "Net-(LED5-A)") (class "Default")
      (node (ref "LED5") (pin "2") (pinfunction "A_2") (pintype "passive"))
      (node (ref "R120") (pin "1") (pinfunction "1_1") (pintype "passive"))
    )
    (net (code "82") (name "Net-(LED6-A)") (class "Default")
      (node (ref "LED6") (pin "2") (pinfunction "A_2") (pintype "passive"))
      (node (ref "R121") (pin "1") (pinfunction "1_1") (pintype "passive"))
    )
    (net (code "83") (name "Net-(LED7-A)") (class "Default")
      (node (ref "LED7") (pin "2") (pinfunction "A_2") (pintype "passive"))
      (node (ref "R122") (pin "1") (pinfunction "1_1") (pintype "passive"))
    )
    (net (code "84") (name "Net-(LED8-A)") (class "Default")
      (node (ref "LED8") (pin "2") (pinfunction "A_2") (pintype "passive"))
      (node (ref "R123") (pin "1") (pinfunction "1_1") (pintype "passive"))
    )
    (net (code "85") (name "Net-(LED9-A)") (class "Default")
      (node (ref "LED9") (pin "2") (pinfunction "A_2") (pintype "passive"))
      (node (ref "R124") (pin "1") (pinfunction "1_1") (pintype "passive"))
    )
    (net (code "86") (name "Net-(LED10-A)") (class "Default")
      (node (ref "LED10") (pin "2") (pinfunction "A_2") (pintype "passive"))
      (node (ref "R125") (pin "1") (pinfunction "1_1") (pintype "passive"))
    )
    (net (code "87") (name "Net-(LED11-A)") (class "Default")
      (node (ref "LED11") (pin "2") (pinfunction "A_2") (pintype "passive"))
      (node (ref "R126") (pin "1") (pinfunction "1_1") (pintype "passive"))
    )
    (net (code "88") (name "Net-(LED12-A)") (class "Default")
      (node (ref "LED12") (pin "2") (pinfunction "A_2") (pintype "passive"))
      (node (ref "R127") (pin "1") (pinfunction "1_1") (pintype "passive"))
    )
    (net (code "89") (name "Net-(LED13-A)") (class "Default")
      (node (ref "LED13") (pin "2") (pinfunction "A_2") (pintype "passive"))
      (node (ref "R128") (pin "1") (pinfunction "1_1") (pintype "passive"))
    )
    (net (code "90") (name "Net-(LED13-K)") (class "Default")
      (node (ref "LED13") (pin "1") (pinfunction "K_1") (pintype "passive"))
      (node (ref "R147") (pin "2") (pinfunction "2_2") (pintype "passive"))
    )
    (net (code "91") (name "Net-(LED14-A)") (class "Default")
      (node (ref "LED14") (pin "2") (pinfunction "A_2") (pintype "passive"))
      (node (ref "R129") (pin "1") (pinfunction "1_1") (pintype "passive"))
    )
    (net (code "92") (name "Net-(LED14-K)") (class "Default")
      (node (ref "LED14") (pin "1") (pinfunction "K_1") (pintype "passive"))
      (node (ref "R142") (pin "2") (pinfunction "2_2") (pintype "passive"))
    )
    (net (code "93") (name "Net-(LED15-A)") (class "Default")
      (node (ref "LED15") (pin "2") (pinfunction "A_2") (pintype "passive"))
      (node (ref "R130") (pin "1") (pinfunction "1_1") (pintype "passive"))
    )
    (net (code "94") (name "Net-(LED15-K)") (class "Default")
      (node (ref "LED15") (pin "1") (pinfunction "K_1") (pintype "passive"))
      (node (ref "R143") (pin "2") (pinfunction "2_2") (pintype "passive"))
    )
    (net (code "95") (name "Net-(LED16-A)") (class "Default")
      (node (ref "LED16") (pin "2") (pinfunction "A_2") (pintype "passive"))
      (node (ref "R131") (pin "2") (pinfunction "2_2") (pintype "passive"))
    )
    (net (code "96") (name "Net-(LED16-K)") (class "Default")
      (node (ref "LED16") (pin "1") (pinfunction "K_1") (pintype "passive"))
      (node (ref "R145") (pin "2") (pinfunction "2_2") (pintype "passive"))
    )
    (net (code "97") (name "Net-(LED17-A)") (class "Default")
      (node (ref "LED17") (pin "2") (pinfunction "A_2") (pintype "passive"))
      (node (ref "R132") (pin "1") (pinfunction "1_1") (pintype "passive"))
    )
    (net (code "98") (name "Net-(LED18-A)") (class "Default")
      (node (ref "LED18") (pin "2") (pinfunction "A_2") (pintype "passive"))
      (node (ref "R134") (pin "1") (pinfunction "1_1") (pintype "passive"))
    )
    (net (code "99") (name "Net-(LED18-K)") (class "Default")
      (node (ref "LED18") (pin "1") (pinfunction "K_1") (pintype "passive"))
      (node (ref "U1") (pin "18") (pinfunction "1Y1_18") (pintype "passive"))
    )
    (net (code "100") (name "Net-(LED19-A)") (class "Default")
      (node (ref "LED19") (pin "2") (pinfunction "A_2") (pintype "passive"))
      (node (ref "R135") (pin "1") (pinfunction "1_1") (pintype "passive"))
    )
    (net (code "101") (name "Net-(LED19-K)") (class "Default")
      (node (ref "LED19") (pin "1") (pinfunction "K_1") (pintype "passive"))
      (node (ref "U1") (pin "16") (pinfunction "1Y2_16") (pintype "passive"))
    )
    (net (code "102") (name "Net-(LED20-A)") (class "Default")
      (node (ref "LED20") (pin "2") (pinfunction "A_2") (pintype "passive"))
      (node (ref "R136") (pin "1") (pinfunction "1_1") (pintype "passive"))
    )
    (net (code "103") (name "Net-(LED20-K)") (class "Default")
      (node (ref "LED20") (pin "1") (pinfunction "K_1") (pintype "passive"))
      (node (ref "U1") (pin "14") (pinfunction "1Y3_14") (pintype "passive"))
    )
    (net (code "104") (name "Net-(LED21-A)") (class "Default")
      (node (ref "LED21") (pin "2") (pinfunction "A_2") (pintype "passive"))
      (node (ref "R137") (pin "1") (pinfunction "1_1") (pintype "passive"))
    )
    (net (code "105") (name "Net-(LED21-K)") (class "Default")
      (node (ref "LED21") (pin "1") (pinfunction "K_1") (pintype "passive"))
      (node (ref "U1") (pin "12") (pinfunction "1Y4_12") (pintype "passive"))
    )
    (net (code "106") (name "Net-(LED22-A)") (class "Default")
      (node (ref "LED22") (pin "2") (pinfunction "A_2") (pintype "passive"))
      (node (ref "R138") (pin "1") (pinfunction "1_1") (pintype "passive"))
    )
    (net (code "107") (name "Net-(LED22-K)") (class "Default")
      (node (ref "LED22") (pin "1") (pinfunction "K_1") (pintype "passive"))
      (node (ref "U1") (pin "9") (pinfunction "2Y1_9") (pintype "passive"))
    )
    (net (code "108") (name "Net-(LED23-A)") (class "Default")
      (node (ref "LED23") (pin "2") (pinfunction "A_2") (pintype "passive"))
      (node (ref "R139") (pin "1") (pinfunction "1_1") (pintype "passive"))
    )
    (net (code "109") (name "Net-(LED23-K)") (class "Default")
      (node (ref "LED23") (pin "1") (pinfunction "K_1") (pintype "passive"))
      (node (ref "U1") (pin "7") (pinfunction "2Y2_7") (pintype "passive"))
    )
    (net (code "110") (name "Net-(LED24-A)") (class "Default")
      (node (ref "LED24") (pin "2") (pinfunction "A_2") (pintype "passive"))
      (node (ref "R140") (pin "1") (pinfunction "1_1") (pintype "passive"))
    )
    (net (code "111") (name "Net-(LED24-K)") (class "Default")
      (node (ref "LED24") (pin "1") (pinfunction "K_1") (pintype "passive"))
      (node (ref "U1") (pin "5") (pinfunction "2Y3_5") (pintype "passive"))
    )
    (net (code "112") (name "Net-(LED25-A)") (class "Default")
      (node (ref "LED25") (pin "2") (pinfunction "A_2") (pintype "passive"))
      (node (ref "R141") (pin "1") (pinfunction "1_1") (pintype "passive"))
    )
    (net (code "113") (name "Net-(LED25-K)") (class "Default")
      (node (ref "LED25") (pin "1") (pinfunction "K_1") (pintype "passive"))
      (node (ref "U1") (pin "3") (pinfunction "2Y4_3") (pintype "passive"))
    )
    (net (code "114") (name "Net-(LED26-A)") (class "Default")
      (node (ref "LED26") (pin "2") (pinfunction "A_2") (pintype "passive"))
      (node (ref "R133") (pin "1") (pinfunction "1_1") (pintype "passive"))
    )
    (net (code "115") (name "Net-(LED27-A)") (class "Default")
      (node (ref "LED27") (pin "2") (pinfunction "A_2") (pintype "passive"))
      (node (ref "R149") (pin "1") (pinfunction "1_1") (pintype "passive"))
    )
    (net (code "116") (name "Net-(LED28-A)") (class "Default")
      (node (ref "LED28") (pin "2") (pinfunction "A_2") (pintype "passive"))
      (node (ref "R150") (pin "2") (pinfunction "2_2") (pintype "passive"))
    )
    (net (code "117") (name "Net-(LED29-A)") (class "Default")
      (node (ref "LED29") (pin "2") (pinfunction "A_2") (pintype "passive"))
      (node (ref "R153") (pin "1") (pinfunction "1_1") (pintype "passive"))
    )
    (net (code "118") (name "Net-(LED30-A)") (class "Default")
      (node (ref "LED30") (pin "2") (pinfunction "A_2") (pintype "passive"))
      (node (ref "R154") (pin "1") (pinfunction "1_1") (pintype "passive"))
    )
    (net (code "119") (name "Net-(LED30-K)") (class "Default")
      (node (ref "LED30") (pin "1") (pinfunction "K_1") (pintype "passive"))
      (node (ref "R174") (pin "2") (pinfunction "2_2") (pintype "passive"))
    )
    (net (code "120") (name "Net-(LED31-A)") (class "Default")
      (node (ref "LED31") (pin "2") (pinfunction "A_2") (pintype "passive"))
      (node (ref "R155") (pin "1") (pinfunction "1_1") (pintype "passive"))
    )
    (net (code "121") (name "Net-(LED31-K)") (class "Default")
      (node (ref "LED31") (pin "1") (pinfunction "K_1") (pintype "passive"))
      (node (ref "R175") (pin "2") (pinfunction "2_2") (pintype "passive"))
    )
    (net (code "122") (name "Net-(LED32-A)") (class "Default")
      (node (ref "LED32") (pin "2") (pinfunction "A_2") (pintype "passive"))
      (node (ref "R156") (pin "1") (pinfunction "1_1") (pintype "passive"))
    )
    (net (code "123") (name "Net-(LED32-K)") (class "Default")
      (node (ref "LED32") (pin "1") (pinfunction "K_1") (pintype "passive"))
      (node (ref "R176") (pin "2") (pinfunction "2_2") (pintype "passive"))
    )
    (net (code "124") (name "Net-(LED33-A)") (class "Default")
      (node (ref "LED33") (pin "2") (pinfunction "A_2") (pintype "passive"))
      (node (ref "R157") (pin "1") (pinfunction "1_1") (pintype "passive"))
    )
    (net (code "125") (name "Net-(LED33-K)") (class "Default")
      (node (ref "LED33") (pin "1") (pinfunction "K_1") (pintype "passive"))
      (node (ref "R179") (pin "2") (pinfunction "2_2") (pintype "passive"))
    )
    (net (code "126") (name "Net-(LED34-A)") (class "Default")
      (node (ref "LED34") (pin "2") (pinfunction "A_2") (pintype "passive"))
      (node (ref "R158") (pin "1") (pinfunction "1_1") (pintype "passive"))
    )
    (net (code "127") (name "Net-(LED34-K)") (class "Default")
      (node (ref "LED34") (pin "1") (pinfunction "K_1") (pintype "passive"))
      (node (ref "R182") (pin "2") (pinfunction "2_2") (pintype "passive"))
    )
    (net (code "128") (name "Net-(LED35-A)") (class "Default")
      (node (ref "LED35") (pin "2") (pinfunction "A_2") (pintype "passive"))
      (node (ref "R159") (pin "1") (pinfunction "1_1") (pintype "passive"))
    )
    (net (code "129") (name "Net-(LED36-A)") (class "Default")
      (node (ref "LED36") (pin "2") (pinfunction "A_2") (pintype "passive"))
      (node (ref "R160") (pin "1") (pinfunction "1_1") (pintype "passive"))
    )
    (net (code "130") (name "Net-(LED36-K)") (class "Default")
      (node (ref "LED36") (pin "1") (pinfunction "K_1") (pintype "passive"))
      (node (ref "R187") (pin "2") (pinfunction "2_2") (pintype "passive"))
    )
    (net (code "131") (name "Net-(LED37-A)") (class "Default")
      (node (ref "LED37") (pin "2") (pinfunction "A_2") (pintype "passive"))
      (node (ref "R161") (pin "1") (pinfunction "1_1") (pintype "passive"))
    )
    (net (code "132") (name "Net-(LED38-A)") (class "Default")
      (node (ref "LED38") (pin "2") (pinfunction "A_2") (pintype "passive"))
      (node (ref "R162") (pin "1") (pinfunction "1_1") (pintype "passive"))
    )
    (net (code "133") (name "Net-(LED39-A)") (class "Default")
      (node (ref "LED39") (pin "2") (pinfunction "A_2") (pintype "passive"))
      (node (ref "R166") (pin "1") (pinfunction "1_1") (pintype "passive"))
    )
    (net (code "134") (name "Net-(LED39-K)") (class "Default")
      (node (ref "LED39") (pin "1") (pinfunction "K_1") (pintype "passive"))
      (node (ref "U4") (pin "18") (pinfunction "1Y1_18") (pintype "passive"))
    )
    (net (code "135") (name "Net-(LED40-A)") (class "Default")
      (node (ref "LED40") (pin "2") (pinfunction "A_2") (pintype "passive"))
      (node (ref "R167") (pin "1") (pinfunction "1_1") (pintype "passive"))
    )
    (net (code "136") (name "Net-(LED40-K)") (class "Default")
      (node (ref "LED40") (pin "1") (pinfunction "K_1") (pintype "passive"))
      (node (ref "U4") (pin "16") (pinfunction "1Y2_16") (pintype "passive"))
    )
    (net (code "137") (name "Net-(LED41-A)") (class "Default")
      (node (ref "LED41") (pin "2") (pinfunction "A_2") (pintype "passive"))
      (node (ref "R168") (pin "1") (pinfunction "1_1") (pintype "passive"))
    )
    (net (code "138") (name "Net-(LED41-K)") (class "Default")
      (node (ref "LED41") (pin "1") (pinfunction "K_1") (pintype "passive"))
      (node (ref "U4") (pin "14") (pinfunction "1Y3_14") (pintype "passive"))
    )
    (net (code "139") (name "Net-(LED42-A)") (class "Default")
      (node (ref "LED42") (pin "2") (pinfunction "A_2") (pintype "passive"))
      (node (ref "R169") (pin "1") (pinfunction "1_1") (pintype "passive"))
    )
    (net (code "140") (name "Net-(LED42-K)") (class "Default")
      (node (ref "LED42") (pin "1") (pinfunction "K_1") (pintype "passive"))
      (node (ref "U4") (pin "12") (pinfunction "1Y4_12") (pintype "passive"))
    )
    (net (code "141") (name "Net-(LED43-A)") (class "Default")
      (node (ref "LED43") (pin "2") (pinfunction "A_2") (pintype "passive"))
      (node (ref "R170") (pin "1") (pinfunction "1_1") (pintype "passive"))
    )
    (net (code "142") (name "Net-(LED43-K)") (class "Default")
      (node (ref "LED43") (pin "1") (pinfunction "K_1") (pintype "passive"))
      (node (ref "U4") (pin "9") (pinfunction "2Y1_9") (pintype "passive"))
    )
    (net (code "143") (name "Net-(LED44-A)") (class "Default")
      (node (ref "LED44") (pin "2") (pinfunction "A_2") (pintype "passive"))
      (node (ref "R171") (pin "1") (pinfunction "1_1") (pintype "passive"))
    )
    (net (code "144") (name "Net-(LED44-K)") (class "Default")
      (node (ref "LED44") (pin "1") (pinfunction "K_1") (pintype "passive"))
      (node (ref "U4") (pin "7") (pinfunction "2Y2_7") (pintype "passive"))
    )
    (net (code "145") (name "Net-(LED45-A)") (class "Default")
      (node (ref "LED45") (pin "2") (pinfunction "A_2") (pintype "passive"))
      (node (ref "R172") (pin "1") (pinfunction "1_1") (pintype "passive"))
    )
    (net (code "146") (name "Net-(LED45-K)") (class "Default")
      (node (ref "LED45") (pin "1") (pinfunction "K_1") (pintype "passive"))
      (node (ref "U4") (pin "5") (pinfunction "2Y3_5") (pintype "passive"))
    )
    (net (code "147") (name "Net-(LED46-A)") (class "Default")
      (node (ref "LED46") (pin "2") (pinfunction "A_2") (pintype "passive"))
      (node (ref "R173") (pin "1") (pinfunction "1_1") (pintype "passive"))
    )
    (net (code "148") (name "Net-(LED46-K)") (class "Default")
      (node (ref "LED46") (pin "1") (pinfunction "K_1") (pintype "passive"))
      (node (ref "U4") (pin "3") (pinfunction "2Y4_3") (pintype "passive"))
    )
    (net (code "149") (name "Net-(LED47-A)") (class "Default")
      (node (ref "LED47") (pin "2") (pinfunction "A_2") (pintype "passive"))
      (node (ref "R192") (pin "1") (pinfunction "1_1") (pintype "passive"))
    )
    (net (code "150") (name "Net-(LED47-K)") (class "Default")
      (node (ref "LED47") (pin "1") (pinfunction "K_1") (pintype "passive"))
      (node (ref "R214") (pin "2") (pinfunction "2_2") (pintype "passive"))
    )
    (net (code "151") (name "Net-(LED48-A)") (class "Default")
      (node (ref "LED48") (pin "2") (pinfunction "A_2") (pintype "passive"))
      (node (ref "R193") (pin "1") (pinfunction "1_1") (pintype "passive"))
    )
    (net (code "152") (name "Net-(LED48-K)") (class "Default")
      (node (ref "LED48") (pin "1") (pinfunction "K_1") (pintype "passive"))
      (node (ref "R215") (pin "2") (pinfunction "2_2") (pintype "passive"))
    )
    (net (code "153") (name "Net-(LED49-A)") (class "Default")
      (node (ref "LED49") (pin "2") (pinfunction "A_2") (pintype "passive"))
      (node (ref "R194") (pin "1") (pinfunction "1_1") (pintype "passive"))
    )
    (net (code "154") (name "Net-(LED49-K)") (class "Default")
      (node (ref "LED49") (pin "1") (pinfunction "K_1") (pintype "passive"))
      (node (ref "R216") (pin "2") (pinfunction "2_2") (pintype "passive"))
    )
    (net (code "155") (name "Net-(LED50-A)") (class "Default")
      (node (ref "LED50") (pin "2") (pinfunction "A_2") (pintype "passive"))
      (node (ref "R195") (pin "1") (pinfunction "1_1") (pintype "passive"))
    )
    (net (code "156") (name "Net-(LED50-K)") (class "Default")
      (node (ref "LED50") (pin "1") (pinfunction "K_1") (pintype "passive"))
      (node (ref "R217") (pin "2") (pinfunction "2_2") (pintype "passive"))
    )
    (net (code "157") (name "Net-(LED51-A)") (class "Default")
      (node (ref "LED51") (pin "2") (pinfunction "A_2") (pintype "passive"))
      (node (ref "R196") (pin "1") (pinfunction "1_1") (pintype "passive"))
    )
    (net (code "158") (name "Net-(LED51-K)") (class "Default")
      (node (ref "LED51") (pin "1") (pinfunction "K_1") (pintype "passive"))
      (node (ref "R218") (pin "2") (pinfunction "2_2") (pintype "passive"))
    )
    (net (code "159") (name "Net-(LED52-A)") (class "Default")
      (node (ref "LED52") (pin "2") (pinfunction "A_2") (pintype "passive"))
      (node (ref "R197") (pin "1") (pinfunction "1_1") (pintype "passive"))
    )
    (net (code "160") (name "Net-(LED53-A)") (class "Default")
      (node (ref "LED53") (pin "2") (pinfunction "A_2") (pintype "passive"))
      (node (ref "R198") (pin "1") (pinfunction "1_1") (pintype "passive"))
    )
    (net (code "161") (name "Net-(LED53-K)") (class "Default")
      (node (ref "LED53") (pin "1") (pinfunction "K_1") (pintype "passive"))
      (node (ref "R221") (pin "2") (pinfunction "2_2") (pintype "passive"))
    )
    (net (code "162") (name "Net-(LED54-A)") (class "Default")
      (node (ref "LED54") (pin "2") (pinfunction "A_2") (pintype "passive"))
      (node (ref "R199") (pin "1") (pinfunction "1_1") (pintype "passive"))
    )
    (net (code "163") (name "Net-(LED55-A)") (class "Default")
      (node (ref "LED55") (pin "2") (pinfunction "A_2") (pintype "passive"))
      (node (ref "R200") (pin "1") (pinfunction "1_1") (pintype "passive"))
    )
    (net (code "164") (name "Net-(LED56-A)") (class "Default")
      (node (ref "LED56") (pin "2") (pinfunction "A_2") (pintype "passive"))
      (node (ref "R201") (pin "1") (pinfunction "1_1") (pintype "passive"))
    )
    (net (code "165") (name "Net-(R224-Pad1)") (class "Default")
      (node (ref "R224") (pin "1") (pinfunction "1_1") (pintype "passive"))
      (node (ref "TP8") (pin "1") (pinfunction "1_1") (pintype "passive"))
    )
    (net (code "166") (name "Net-(R225-Pad2)") (class "Default")
      (node (ref "R225") (pin "2") (pinfunction "2_2") (pintype "passive"))
      (node (ref "TP9") (pin "1") (pinfunction "1_1") (pintype "passive"))
    )
    (net (code "167") (name "Net-(R226-Pad1)") (class "Default")
      (node (ref "R226") (pin "1") (pinfunction "1_1") (pintype "passive"))
      (node (ref "TP10") (pin "1") (pinfunction "1_1") (pintype "passive"))
    )
    (net (code "168") (name "Net-(R227-Pad2)") (class "Default")
      (node (ref "R227") (pin "2") (pinfunction "2_2") (pintype "passive"))
      (node (ref "TP11") (pin "1") (pinfunction "1_1") (pintype "passive"))
    )
    (net (code "169") (name "Net-(U2-1A)") (class "Default")
      (node (ref "R148") (pin "2") (pinfunction "2_2") (pintype "passive"))
      (node (ref "U2") (pin "1") (pinfunction "1A_1") (pintype "passive"))
    )
    (net (code "170") (name "Net-(U2-2A)") (class "Default")
      (node (ref "R151") (pin "2") (pinfunction "2_2") (pintype "passive"))
      (node (ref "U2") (pin "3") (pinfunction "2A_3") (pintype "passive"))
    )
    (net (code "171") (name "Net-(U2-3A)") (class "Default")
      (node (ref "R152") (pin "2") (pinfunction "2_2") (pintype "passive"))
      (node (ref "U2") (pin "5") (pinfunction "3A_5") (pintype "passive"))
    )
    (net (code "172") (name "Net-(U2-4A)") (class "Default")
      (node (ref "R163") (pin "2") (pinfunction "2_2") (pintype "passive"))
      (node (ref "U2") (pin "9") (pinfunction "4A_9") (pintype "passive"))
    )
    (net (code "173") (name "Net-(U2-5A)") (class "Default")
      (node (ref "R164") (pin "2") (pinfunction "2_2") (pintype "passive"))
      (node (ref "U2") (pin "11") (pinfunction "5A_11") (pintype "passive"))
    )
    (net (code "174") (name "Net-(U2-6A)") (class "Default")
      (node (ref "R165") (pin "2") (pinfunction "2_2") (pintype "passive"))
      (node (ref "U2") (pin "13") (pinfunction "6A_13") (pintype "passive"))
    )
    (net (code "175") (name "Net-(U3-1A)") (class "Default")
      (node (ref "R177") (pin "2") (pinfunction "2_2") (pintype "passive"))
      (node (ref "U3") (pin "1") (pinfunction "1A_1") (pintype "passive"))
    )
    (net (code "176") (name "Net-(U3-1Y)") (class "Default")
      (node (ref "R178") (pin "1") (pinfunction "1_1") (pintype "passive"))
      (node (ref "U3") (pin "2") (pinfunction "1Y_2") (pintype "passive"))
    )
    (net (code "177") (name "Net-(U3-2A)") (class "Default")
      (node (ref "R180") (pin "2") (pinfunction "2_2") (pintype "passive"))
      (node (ref "U3") (pin "3") (pinfunction "2A_3") (pintype "passive"))
    )
    (net (code "178") (name "Net-(U3-2Y)") (class "Default")
      (node (ref "R181") (pin "1") (pinfunction "1_1") (pintype "passive"))
      (node (ref "U3") (pin "4") (pinfunction "2Y_4") (pintype "passive"))
    )
    (net (code "179") (name "Net-(U3-3A)") (class "Default")
      (node (ref "R183") (pin "2") (pinfunction "2_2") (pintype "passive"))
      (node (ref "U3") (pin "5") (pinfunction "3A_5") (pintype "passive"))
    )
    (net (code "180") (name "Net-(U3-3Y)") (class "Default")
      (node (ref "R184") (pin "1") (pinfunction "1_1") (pintype "passive"))
      (node (ref "U3") (pin "6") (pinfunction "3Y_6") (pintype "passive"))
    )
    (net (code "181") (name "Net-(U3-4A)") (class "Default")
      (node (ref "R185") (pin "2") (pinfunction "2_2") (pintype "passive"))
      (node (ref "U3") (pin "9") (pinfunction "4A_9") (pintype "passive"))
    )
    (net (code "182") (name "Net-(U3-4Y)") (class "Default")
      (node (ref "R186") (pin "1") (pinfunction "1_1") (pintype "passive"))
      (node (ref "U3") (pin "8") (pinfunction "4Y_8") (pintype "passive"))
    )
    (net (code "183") (name "Net-(U3-5A)") (class "Default")
      (node (ref "R188") (pin "2") (pinfunction "2_2") (pintype "passive"))
      (node (ref "U3") (pin "11") (pinfunction "5A_11") (pintype "passive"))
    )
    (net (code "184") (name "Net-(U3-5Y)") (class "Default")
      (node (ref "R189") (pin "1") (pinfunction "1_1") (pintype "passive"))
      (node (ref "U3") (pin "10") (pinfunction "5Y_10") (pintype "passive"))
    )
    (net (code "185") (name "Net-(U3-6A)") (class "Default")
      (node (ref "R190") (pin "2") (pinfunction "2_2") (pintype "passive"))
      (node (ref "U3") (pin "13") (pinfunction "6A_13") (pintype "passive"))
    )
    (net (code "186") (name "Net-(U3-6Y)") (class "Default")
      (node (ref "R191") (pin "1") (pinfunction "1_1") (pintype "passive"))
      (node (ref "U3") (pin "12") (pinfunction "6Y_12") (pintype "passive"))
    )
    (net (code "187") (name "Net-(U5-1A)") (class "Default")
      (node (ref "R202") (pin "2") (pinfunction "2_2") (pintype "passive"))
      (node (ref "U5") (pin "1") (pinfunction "1A_1") (pintype "passive"))
    )
    (net (code "188") (name "Net-(U5-1Y)") (class "Default")
      (node (ref "R203") (pin "1") (pinfunction "1_1") (pintype "passive"))
      (node (ref "U5") (pin "2") (pinfunction "1Y_2") (pintype "passive"))
    )
    (net (code "189") (name "Net-(U5-2A)") (class "Default")
      (node (ref "R204") (pin "2") (pinfunction "2_2") (pintype "passive"))
      (node (ref "U5") (pin "3") (pinfunction "2A_3") (pintype "passive"))
    )
    (net (code "190") (name "Net-(U5-2Y)") (class "Default")
      (node (ref "R205") (pin "1") (pinfunction "1_1") (pintype "passive"))
      (node (ref "U5") (pin "4") (pinfunction "2Y_4") (pintype "passive"))
    )
    (net (code "191") (name "Net-(U5-3A)") (class "Default")
      (node (ref "R206") (pin "2") (pinfunction "2_2") (pintype "passive"))
      (node (ref "U5") (pin "5") (pinfunction "3A_5") (pintype "passive"))
    )
    (net (code "192") (name "Net-(U5-3Y)") (class "Default")
      (node (ref "R207") (pin "1") (pinfunction "1_1") (pintype "passive"))
      (node (ref "U5") (pin "6") (pinfunction "3Y_6") (pintype "passive"))
    )
    (net (code "193") (name "Net-(U5-4A)") (class "Default")
      (node (ref "R208") (pin "2") (pinfunction "2_2") (pintype "passive"))
      (node (ref "U5") (pin "9") (pinfunction "4A_9") (pintype "passive"))
    )
    (net (code "194") (name "Net-(U5-4Y)") (class "Default")
      (node (ref "R209") (pin "1") (pinfunction "1_1") (pintype "passive"))
      (node (ref "U5") (pin "8") (pinfunction "4Y_8") (pintype "passive"))
    )
    (net (code "195") (name "Net-(U5-5A)") (class "Default")
      (node (ref "R210") (pin "2") (pinfunction "2_2") (pintype "passive"))
      (node (ref "U5") (pin "11") (pinfunction "5A_11") (pintype "passive"))
    )
    (net (code "196") (name "Net-(U5-5Y)") (class "Default")
      (node (ref "R211") (pin "1") (pinfunction "1_1") (pintype "passive"))
      (node (ref "U5") (pin "10") (pinfunction "5Y_10") (pintype "passive"))
    )
    (net (code "197") (name "Net-(U5-6A)") (class "Default")
      (node (ref "R212") (pin "2") (pinfunction "2_2") (pintype "passive"))
      (node (ref "U5") (pin "13") (pinfunction "6A_13") (pintype "passive"))
    )
    (net (code "198") (name "Net-(U5-6Y)") (class "Default")
      (node (ref "R213") (pin "1") (pinfunction "1_1") (pintype "passive"))
      (node (ref "U5") (pin "12") (pinfunction "6Y_12") (pintype "passive"))
    )
    (net (code "199") (name "Net-(U6-1A)") (class "Default")
      (node (ref "R219") (pin "2") (pinfunction "2_2") (pintype "passive"))
      (node (ref "U6") (pin "1") (pinfunction "1A_1") (pintype "passive"))
    )
    (net (code "200") (name "Net-(U6-2A)") (class "Default")
      (node (ref "R220") (pin "2") (pinfunction "2_2") (pintype "passive"))
      (node (ref "U6") (pin "3") (pinfunction "2A_3") (pintype "passive"))
    )
    (net (code "201") (name "Net-(U6-3A)") (class "Default")
      (node (ref "R222") (pin "2") (pinfunction "2_2") (pintype "passive"))
      (node (ref "U6") (pin "5") (pinfunction "3A_5") (pintype "passive"))
    )
    (net (code "202") (name "Net-(U6-4A)") (class "Default")
      (node (ref "R223") (pin "2") (pinfunction "2_2") (pintype "passive"))
      (node (ref "U6") (pin "9") (pinfunction "4A_9") (pintype "passive"))
    )
    (net (code "203") (name "Net-(U6-5A)") (class "Default")
      (node (ref "R224") (pin "2") (pinfunction "2_2") (pintype "passive"))
      (node (ref "U6") (pin "11") (pinfunction "5A_11") (pintype "passive"))
    )
    (net (code "204") (name "Net-(U6-5Y)") (class "Default")
      (node (ref "R225") (pin "1") (pinfunction "1_1") (pintype "passive"))
      (node (ref "U6") (pin "10") (pinfunction "5Y_10") (pintype "passive"))
    )
    (net (code "205") (name "Net-(U6-6A)") (class "Default")
      (node (ref "R226") (pin "2") (pinfunction "2_2") (pintype "passive"))
      (node (ref "U6") (pin "13") (pinfunction "6A_13") (pintype "passive"))
    )
    (net (code "206") (name "Net-(U6-6Y)") (class "Default")
      (node (ref "R227") (pin "1") (pinfunction "1_1") (pintype "passive"))
      (node (ref "U6") (pin "12") (pinfunction "6Y_12") (pintype "passive"))
    )
  )
)
